# TactJam_Assembly.net
KiCad netlist of a schematic drawn in EasyEDA
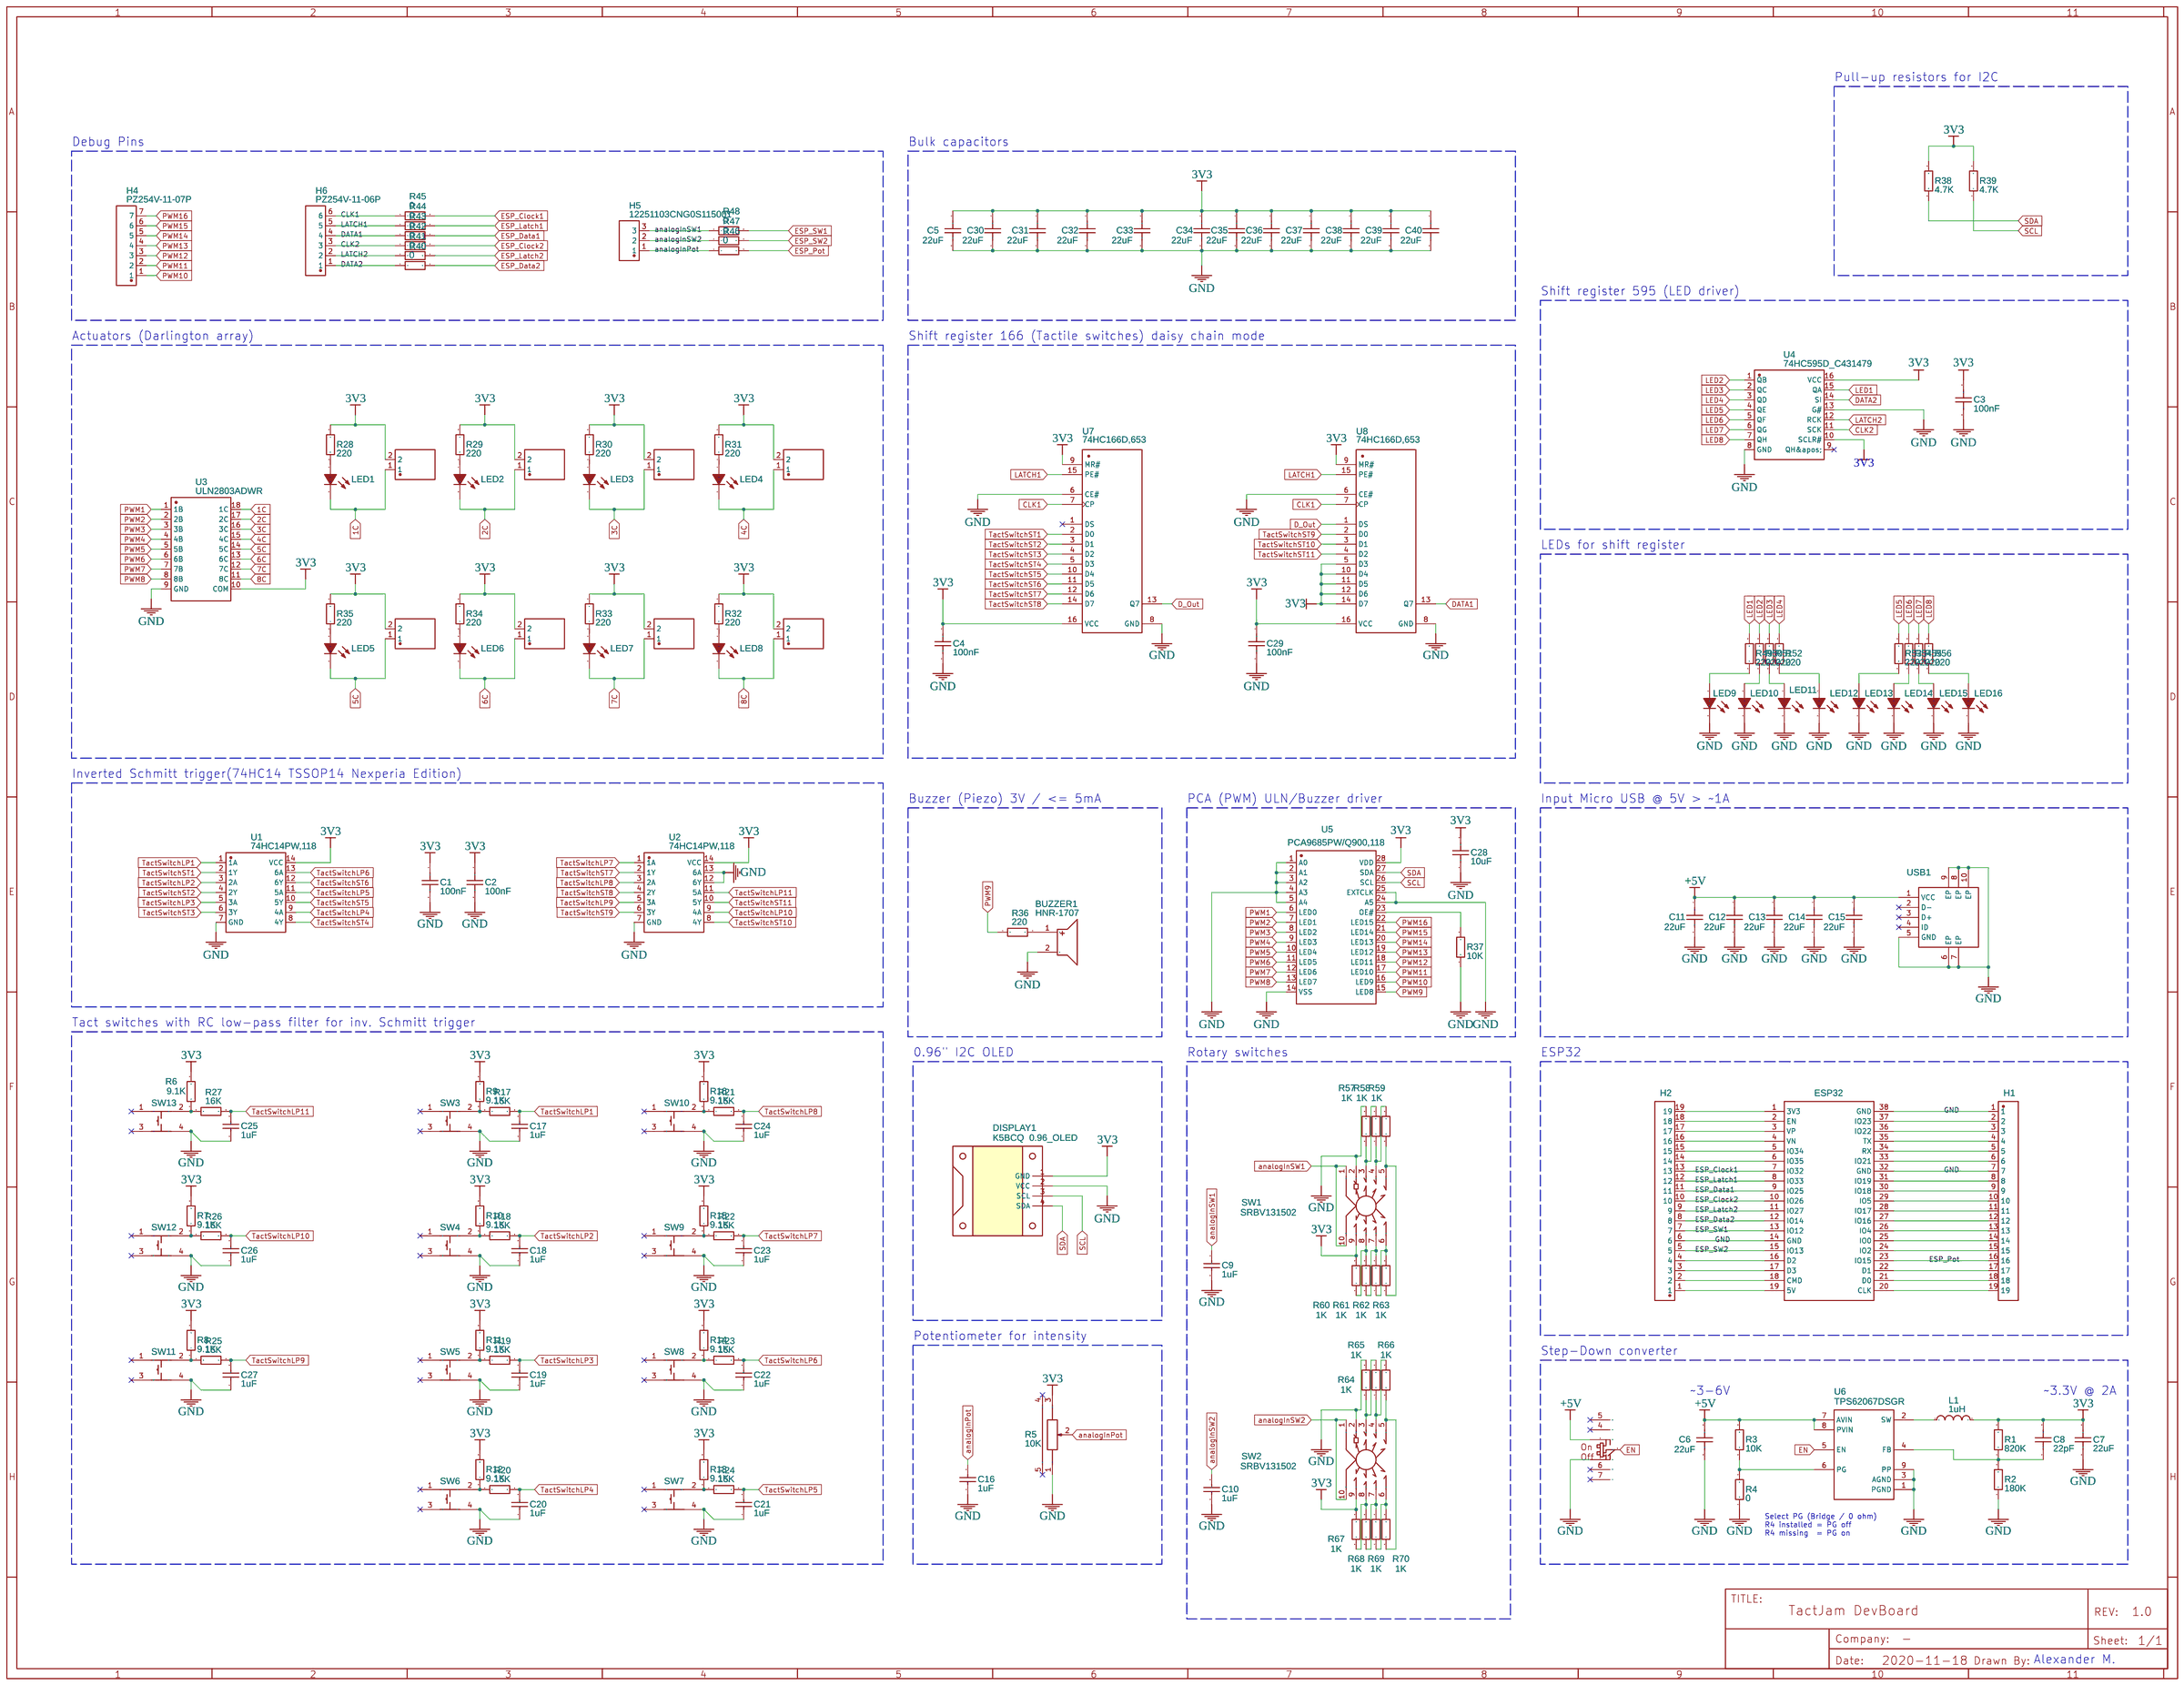
[diagram p0: schematic sheet]

(export (version "E")
  (design (tool "Eeschema 10.0.6"))
  (components
    (comp (ref "BUZZER1")
      (value "HNR-1707")
      (fields (field (name "BOM_Supplier Part") "C129400"))
      (libsource (lib "") (part "HNR-1707"))
    )
    (comp (ref "C1")
      (value "100nF")
      (fields
        (field (name "BOM_Manufacturer Part") "CL05B104KB54PNC")
        (field (name "BOM_Supplier Part") "C307331")
      )
      (libsource (lib "") (part "CL05B104KB54PNC"))
    )
    (comp (ref "C2")
      (value "100nF")
      (fields
        (field (name "BOM_Manufacturer Part") "CL05B104KB54PNC")
        (field (name "BOM_Supplier Part") "C307331")
      )
      (libsource (lib "") (part "CL05B104KB54PNC"))
    )
    (comp (ref "C3")
      (value "100nF")
      (fields
        (field (name "BOM_Manufacturer Part") "CL05B104KB54PNC")
        (field (name "BOM_Supplier Part") "C307331")
      )
      (libsource (lib "") (part "CL05B104KB54PNC"))
    )
    (comp (ref "C4")
      (value "100nF")
      (fields
        (field (name "BOM_Manufacturer Part") "CL05B104KB54PNC")
        (field (name "BOM_Supplier Part") "C307331")
      )
      (libsource (lib "") (part "CL05B104KB54PNC"))
    )
    (comp (ref "C5")
      (value "22uF")
      (fields
        (field (name "BOM_Manufacturer Part") "CL10A226MQ8NRNC")
        (field (name "BOM_Supplier Part") "C59461")
      )
      (libsource (lib "") (part "CL10A226MQ8NRNC"))
    )
    (comp (ref "C6")
      (value "22uF")
      (fields
        (field (name "BOM_Manufacturer Part") "CL10A226MQ8NRNC")
        (field (name "BOM_Supplier Part") "C59461")
      )
      (libsource (lib "") (part "CL10A226MQ8NRNC"))
    )
    (comp (ref "C7")
      (value "22uF")
      (fields
        (field (name "BOM_Manufacturer Part") "CL10A226MQ8NRNC")
        (field (name "BOM_Supplier Part") "C59461")
      )
      (libsource (lib "") (part "CL10A226MQ8NRNC_1"))
    )
    (comp (ref "C8")
      (value "22pF")
      (fields
        (field (name "BOM_Manufacturer Part") "CL05C220JB5NNNC")
        (field (name "BOM_Supplier Part") "C70464")
      )
      (libsource (lib "") (part "CL05C220JB5NNNC"))
    )
    (comp (ref "C9")
      (value "1uF")
      (fields
        (field (name "BOM_Manufacturer Part") "CL10B105KA8NNNC")
        (field (name "BOM_Supplier Part") "C29936")
      )
      (libsource (lib "") (part "CL10B105KA8NNNC"))
    )
    (comp (ref "C10")
      (value "1uF")
      (fields
        (field (name "BOM_Manufacturer Part") "CL10B105KA8NNNC")
        (field (name "BOM_Supplier Part") "C29936")
      )
      (libsource (lib "") (part "CL10B105KA8NNNC"))
    )
    (comp (ref "C11")
      (value "22uF")
      (fields
        (field (name "BOM_Manufacturer Part") "CL10A226MQ8NRNC")
        (field (name "BOM_Supplier Part") "C59461")
      )
      (libsource (lib "") (part "CL10A226MQ8NRNC"))
    )
    (comp (ref "C12")
      (value "22uF")
      (fields
        (field (name "BOM_Manufacturer Part") "CL10A226MQ8NRNC")
        (field (name "BOM_Supplier Part") "C59461")
      )
      (libsource (lib "") (part "CL10A226MQ8NRNC"))
    )
    (comp (ref "C13")
      (value "22uF")
      (fields
        (field (name "BOM_Manufacturer Part") "CL10A226MQ8NRNC")
        (field (name "BOM_Supplier Part") "C59461")
      )
      (libsource (lib "") (part "CL10A226MQ8NRNC"))
    )
    (comp (ref "C14")
      (value "22uF")
      (fields
        (field (name "BOM_Manufacturer Part") "CL10A226MQ8NRNC")
        (field (name "BOM_Supplier Part") "C59461")
      )
      (libsource (lib "") (part "CL10A226MQ8NRNC"))
    )
    (comp (ref "C15")
      (value "22uF")
      (fields
        (field (name "BOM_Manufacturer Part") "CL10A226MQ8NRNC")
        (field (name "BOM_Supplier Part") "C59461")
      )
      (libsource (lib "") (part "CL10A226MQ8NRNC"))
    )
    (comp (ref "C16")
      (value "1uF")
      (fields
        (field (name "BOM_Manufacturer Part") "CL10B105KA8NNNC")
        (field (name "BOM_Supplier Part") "C29936")
      )
      (libsource (lib "") (part "CL10B105KA8NNNC"))
    )
    (comp (ref "C17")
      (value "1uF")
      (fields
        (field (name "BOM_Manufacturer Part") "CL10B105KA8NNNC")
        (field (name "BOM_Supplier Part") "C29936")
      )
      (libsource (lib "") (part "CL10B105KA8NNNC"))
    )
    (comp (ref "C18")
      (value "1uF")
      (fields
        (field (name "BOM_Manufacturer Part") "CL10B105KA8NNNC")
        (field (name "BOM_Supplier Part") "C29936")
      )
      (libsource (lib "") (part "CL10B105KA8NNNC"))
    )
    (comp (ref "C19")
      (value "1uF")
      (fields
        (field (name "BOM_Manufacturer Part") "CL10B105KA8NNNC")
        (field (name "BOM_Supplier Part") "C29936")
      )
      (libsource (lib "") (part "CL10B105KA8NNNC"))
    )
    (comp (ref "C20")
      (value "1uF")
      (fields
        (field (name "BOM_Manufacturer Part") "CL10B105KA8NNNC")
        (field (name "BOM_Supplier Part") "C29936")
      )
      (libsource (lib "") (part "CL10B105KA8NNNC"))
    )
    (comp (ref "C21")
      (value "1uF")
      (fields
        (field (name "BOM_Manufacturer Part") "CL10B105KA8NNNC")
        (field (name "BOM_Supplier Part") "C29936")
      )
      (libsource (lib "") (part "CL10B105KA8NNNC"))
    )
    (comp (ref "C22")
      (value "1uF")
      (fields
        (field (name "BOM_Manufacturer Part") "CL10B105KA8NNNC")
        (field (name "BOM_Supplier Part") "C29936")
      )
      (libsource (lib "") (part "CL10B105KA8NNNC"))
    )
    (comp (ref "C23")
      (value "1uF")
      (fields
        (field (name "BOM_Manufacturer Part") "CL10B105KA8NNNC")
        (field (name "BOM_Supplier Part") "C29936")
      )
      (libsource (lib "") (part "CL10B105KA8NNNC"))
    )
    (comp (ref "C24")
      (value "1uF")
      (fields
        (field (name "BOM_Manufacturer Part") "CL10B105KA8NNNC")
        (field (name "BOM_Supplier Part") "C29936")
      )
      (libsource (lib "") (part "CL10B105KA8NNNC"))
    )
    (comp (ref "C25")
      (value "1uF")
      (fields
        (field (name "BOM_Manufacturer Part") "CL10B105KA8NNNC")
        (field (name "BOM_Supplier Part") "C29936")
      )
      (libsource (lib "") (part "CL10B105KA8NNNC"))
    )
    (comp (ref "C26")
      (value "1uF")
      (fields
        (field (name "BOM_Manufacturer Part") "CL10B105KA8NNNC")
        (field (name "BOM_Supplier Part") "C29936")
      )
      (libsource (lib "") (part "CL10B105KA8NNNC"))
    )
    (comp (ref "C27")
      (value "1uF")
      (fields
        (field (name "BOM_Manufacturer Part") "CL10B105KA8NNNC")
        (field (name "BOM_Supplier Part") "C29936")
      )
      (libsource (lib "") (part "CL10B105KA8NNNC"))
    )
    (comp (ref "C28")
      (value "10uF")
      (fields
        (field (name "BOM_Manufacturer Part") "CL10A106MA8NRNC")
        (field (name "BOM_Supplier Part") "C96446")
      )
      (libsource (lib "") (part "CL10A106MA8NRNC"))
    )
    (comp (ref "C29")
      (value "100nF")
      (fields
        (field (name "BOM_Manufacturer Part") "CL05B104KB54PNC")
        (field (name "BOM_Supplier Part") "C307331")
      )
      (libsource (lib "") (part "CL05B104KB54PNC"))
    )
    (comp (ref "C30")
      (value "22uF")
      (fields
        (field (name "BOM_Manufacturer Part") "CL10A226MQ8NRNC")
        (field (name "BOM_Supplier Part") "C59461")
      )
      (libsource (lib "") (part "CL10A226MQ8NRNC"))
    )
    (comp (ref "C31")
      (value "22uF")
      (fields
        (field (name "BOM_Manufacturer Part") "CL10A226MQ8NRNC")
        (field (name "BOM_Supplier Part") "C59461")
      )
      (libsource (lib "") (part "CL10A226MQ8NRNC"))
    )
    (comp (ref "C32")
      (value "22uF")
      (fields
        (field (name "BOM_Manufacturer Part") "CL10A226MQ8NRNC")
        (field (name "BOM_Supplier Part") "C59461")
      )
      (libsource (lib "") (part "CL10A226MQ8NRNC"))
    )
    (comp (ref "C33")
      (value "22uF")
      (fields
        (field (name "BOM_Manufacturer Part") "CL10A226MQ8NRNC")
        (field (name "BOM_Supplier Part") "C59461")
      )
      (libsource (lib "") (part "CL10A226MQ8NRNC"))
    )
    (comp (ref "C34")
      (value "22uF")
      (fields
        (field (name "BOM_Manufacturer Part") "CL10A226MQ8NRNC")
        (field (name "BOM_Supplier Part") "C59461")
      )
      (libsource (lib "") (part "CL10A226MQ8NRNC"))
    )
    (comp (ref "C35")
      (value "22uF")
      (fields
        (field (name "BOM_Manufacturer Part") "CL10A226MQ8NRNC")
        (field (name "BOM_Supplier Part") "C59461")
      )
      (libsource (lib "") (part "CL10A226MQ8NRNC"))
    )
    (comp (ref "C36")
      (value "22uF")
      (fields
        (field (name "BOM_Manufacturer Part") "CL10A226MQ8NRNC")
        (field (name "BOM_Supplier Part") "C59461")
      )
      (libsource (lib "") (part "CL10A226MQ8NRNC"))
    )
    (comp (ref "C37")
      (value "22uF")
      (fields
        (field (name "BOM_Manufacturer Part") "CL10A226MQ8NRNC")
        (field (name "BOM_Supplier Part") "C59461")
      )
      (libsource (lib "") (part "CL10A226MQ8NRNC"))
    )
    (comp (ref "C38")
      (value "22uF")
      (fields
        (field (name "BOM_Manufacturer Part") "CL10A226MQ8NRNC")
        (field (name "BOM_Supplier Part") "C59461")
      )
      (libsource (lib "") (part "CL10A226MQ8NRNC"))
    )
    (comp (ref "C39")
      (value "22uF")
      (fields
        (field (name "BOM_Manufacturer Part") "CL10A226MQ8NRNC")
        (field (name "BOM_Supplier Part") "C59461")
      )
      (libsource (lib "") (part "CL10A226MQ8NRNC"))
    )
    (comp (ref "C40")
      (value "22uF")
      (fields
        (field (name "BOM_Manufacturer Part") "CL10A226MQ8NRNC")
        (field (name "BOM_Supplier Part") "C59461")
      )
      (libsource (lib "") (part "CL10A226MQ8NRNC"))
    )
    (comp (ref "CONNECTOR1")
      (value "Connector")
      (fields (field (name "BOM_Supplier Part") "C132463"))
      (libsource (lib "") (part "2501SB-2P"))
    )
    (comp (ref "CONNECTOR2")
      (value "Connector")
      (fields (field (name "BOM_Supplier Part") "C63855"))
      (libsource (lib "") (part "2501SB-2P"))
    )
    (comp (ref "CONNECTOR3")
      (value "Connector")
      (fields (field (name "BOM_Supplier Part") "C132463"))
      (libsource (lib "") (part "2501SB-2P"))
    )
    (comp (ref "CONNECTOR4")
      (value "Connector")
      (fields (field (name "BOM_Supplier Part") "C132463"))
      (libsource (lib "") (part "2501SB-2P"))
    )
    (comp (ref "CONNECTOR5")
      (value "Connector")
      (fields (field (name "BOM_Supplier Part") "C132463"))
      (libsource (lib "") (part "2501SB-2P"))
    )
    (comp (ref "CONNECTOR6")
      (value "Connector")
      (fields (field (name "BOM_Supplier Part") "C132463"))
      (libsource (lib "") (part "2501SB-2P"))
    )
    (comp (ref "CONNECTOR7")
      (value "Connector")
      (fields (field (name "BOM_Supplier Part") "C132463"))
      (libsource (lib "") (part "2501SB-2P"))
    )
    (comp (ref "CONNECTOR8")
      (value "Connector")
      (fields (field (name "BOM_Supplier Part") "C132463"))
      (libsource (lib "") (part "2501SB-2P"))
    )
    (comp (ref "DISPLAY1")
      (value "K5BCQ  0.96_OLED")
      (fields (field (name "BOM_Manufacturer Part") "0.96 OLED"))
      (libsource (lib "") (part "K5BCQ  0.96_OLED"))
    )
    (comp (ref "ESP1") (value "ESP32") (libsource (lib "") (part "ESP32")))
    (comp (ref "H1") (value "C247840") (libsource (lib "") (part "C247840_1")))
    (comp (ref "H2") (value "C247840") (libsource (lib "") (part "C247840")))
    (comp (ref "H4")
      (value "PZ254V-11-07P")
      (fields (field (name "BOM_Supplier Part") "C492406"))
      (libsource (lib "") (part "PZ254V-11-07P"))
    )
    (comp (ref "H5")
      (value "12251103CNG0S115001")
      (fields (field (name "BOM_Supplier Part") "C429954"))
      (libsource (lib "") (part "12251103CNG0S115001"))
    )
    (comp (ref "H6")
      (value "PZ254V-11-06P")
      (fields (field (name "BOM_Supplier Part") "C492405"))
      (libsource (lib "") (part "PZ254V-11-06P"))
    )
    (comp (ref "L1")
      (value "1uH")
      (fields
        (field (name "BOM_Manufacturer Part") "LQH44PN1R0NP0L")
        (field (name "BOM_Supplier Part") "C98026")
      )
      (libsource (lib "") (part "LQH44PN1R0NP0L"))
    )
    (comp (ref "LED1")
      (value "19-217/GHC-YR1S2/3T")
      (fields (field (name "BOM_Supplier Part") "C72043"))
      (libsource (lib "") (part "19-217/GHC-YR1S2/3T"))
    )
    (comp (ref "LED2")
      (value "19-217/GHC-YR1S2/3T")
      (fields (field (name "BOM_Supplier Part") "C72043"))
      (libsource (lib "") (part "19-217/GHC-YR1S2/3T"))
    )
    (comp (ref "LED3")
      (value "19-217/GHC-YR1S2/3T")
      (fields (field (name "BOM_Supplier Part") "C72043"))
      (libsource (lib "") (part "19-217/GHC-YR1S2/3T"))
    )
    (comp (ref "LED4")
      (value "19-217/GHC-YR1S2/3T")
      (fields (field (name "BOM_Supplier Part") "C72043"))
      (libsource (lib "") (part "19-217/GHC-YR1S2/3T"))
    )
    (comp (ref "LED5")
      (value "19-217/GHC-YR1S2/3T")
      (fields (field (name "BOM_Supplier Part") "C72043"))
      (libsource (lib "") (part "19-217/GHC-YR1S2/3T"))
    )
    (comp (ref "LED6")
      (value "19-217/GHC-YR1S2/3T")
      (fields (field (name "BOM_Supplier Part") "C72043"))
      (libsource (lib "") (part "19-217/GHC-YR1S2/3T"))
    )
    (comp (ref "LED7")
      (value "19-217/GHC-YR1S2/3T")
      (fields (field (name "BOM_Supplier Part") "C72043"))
      (libsource (lib "") (part "19-217/GHC-YR1S2/3T"))
    )
    (comp (ref "LED8")
      (value "19-217/GHC-YR1S2/3T")
      (fields (field (name "BOM_Supplier Part") "C72043"))
      (libsource (lib "") (part "19-217/GHC-YR1S2/3T"))
    )
    (comp (ref "LED9")
      (value "19-217/GHC-YR1S2/3T")
      (fields (field (name "BOM_Supplier Part") "C72043"))
      (libsource (lib "") (part "19-217/GHC-YR1S2/3T"))
    )
    (comp (ref "LED10")
      (value "19-217/GHC-YR1S2/3T")
      (fields (field (name "BOM_Supplier Part") "C72043"))
      (libsource (lib "") (part "19-217/GHC-YR1S2/3T"))
    )
    (comp (ref "LED11")
      (value "19-217/GHC-YR1S2/3T")
      (fields (field (name "BOM_Supplier Part") "C72043"))
      (libsource (lib "") (part "19-217/GHC-YR1S2/3T"))
    )
    (comp (ref "LED12")
      (value "19-217/GHC-YR1S2/3T")
      (fields (field (name "BOM_Supplier Part") "C72043"))
      (libsource (lib "") (part "19-217/GHC-YR1S2/3T"))
    )
    (comp (ref "LED13")
      (value "19-217/GHC-YR1S2/3T")
      (fields (field (name "BOM_Supplier Part") "C72043"))
      (libsource (lib "") (part "19-217/GHC-YR1S2/3T"))
    )
    (comp (ref "LED14")
      (value "19-217/GHC-YR1S2/3T")
      (fields (field (name "BOM_Supplier Part") "C72043"))
      (libsource (lib "") (part "19-217/GHC-YR1S2/3T"))
    )
    (comp (ref "LED15")
      (value "19-217/GHC-YR1S2/3T")
      (fields (field (name "BOM_Supplier Part") "C72043"))
      (libsource (lib "") (part "19-217/GHC-YR1S2/3T"))
    )
    (comp (ref "LED16")
      (value "19-217/GHC-YR1S2/3T")
      (fields (field (name "BOM_Supplier Part") "C72043"))
      (libsource (lib "") (part "19-217/GHC-YR1S2/3T"))
    )
    (comp (ref "R1")
      (value "820K")
      (fields
        (field (name "BOM_Manufacturer Part") "TC0325B8203T5E")
        (field (name "BOM_Supplier Part") "C53198")
      )
      (libsource (lib "") (part "TC0325B8203T5E"))
    )
    (comp (ref "R2")
      (value "180K")
      (fields
        (field (name "BOM_Manufacturer Part") "0603WAF1803T5E")
        (field (name "BOM_Supplier Part") "C22827")
      )
      (libsource (lib "") (part "0603WAF1803T5E"))
    )
    (comp (ref "R3")
      (value "10K")
      (fields
        (field (name "BOM_Manufacturer Part") "0603WAF1002T5E")
        (field (name "BOM_Supplier Part") "C25804")
      )
      (libsource (lib "") (part "0603WAF1002T5E"))
    )
    (comp (ref "R4")
      (value "0")
      (fields
        (field (name "BOM_Manufacturer Part") "0603WAF0000T5E")
        (field (name "BOM_Supplier Part") "C21189")
      )
      (libsource (lib "") (part "0603WAF0000T5E_1"))
    )
    (comp (ref "R5")
      (value "10K")
      (fields
        (field (name "BOM_Manufacturer Part") "RK09K1130A5R")
        (field (name "BOM_Supplier Part") "C209779")
      )
      (libsource (lib "") (part "RK09K1130A5R"))
    )
    (comp (ref "R6")
      (value "9.1K")
      (fields
        (field (name "BOM_Manufacturer Part") "TC0350D9101T5E")
        (field (name "BOM_Supplier Part") "C98730")
      )
      (libsource (lib "") (part "TC0350D9101T5E"))
    )
    (comp (ref "R7")
      (value "9.1K")
      (fields
        (field (name "BOM_Manufacturer Part") "TC0350D9101T5E")
        (field (name "BOM_Supplier Part") "C98730")
      )
      (libsource (lib "") (part "TC0350D9101T5E"))
    )
    (comp (ref "R8")
      (value "9.1K")
      (fields
        (field (name "BOM_Manufacturer Part") "TC0350D9101T5E")
        (field (name "BOM_Supplier Part") "C98730")
      )
      (libsource (lib "") (part "TC0350D9101T5E"))
    )
    (comp (ref "R9")
      (value "9.1K")
      (fields
        (field (name "BOM_Manufacturer Part") "TC0350D9101T5E")
        (field (name "BOM_Supplier Part") "C98730")
      )
      (libsource (lib "") (part "TC0350D9101T5E"))
    )
    (comp (ref "R10")
      (value "9.1K")
      (fields
        (field (name "BOM_Manufacturer Part") "TC0350D9101T5E")
        (field (name "BOM_Supplier Part") "C98730")
      )
      (libsource (lib "") (part "TC0350D9101T5E"))
    )
    (comp (ref "R11")
      (value "9.1K")
      (fields
        (field (name "BOM_Manufacturer Part") "TC0350D9101T5E")
        (field (name "BOM_Supplier Part") "C98730")
      )
      (libsource (lib "") (part "TC0350D9101T5E"))
    )
    (comp (ref "R12")
      (value "9.1K")
      (fields
        (field (name "BOM_Manufacturer Part") "TC0350D9101T5E")
        (field (name "BOM_Supplier Part") "C98730")
      )
      (libsource (lib "") (part "TC0350D9101T5E"))
    )
    (comp (ref "R13")
      (value "9.1K")
      (fields
        (field (name "BOM_Manufacturer Part") "TC0350D9101T5E")
        (field (name "BOM_Supplier Part") "C98730")
      )
      (libsource (lib "") (part "TC0350D9101T5E"))
    )
    (comp (ref "R14")
      (value "9.1K")
      (fields
        (field (name "BOM_Manufacturer Part") "TC0350D9101T5E")
        (field (name "BOM_Supplier Part") "C98730")
      )
      (libsource (lib "") (part "TC0350D9101T5E"))
    )
    (comp (ref "R15")
      (value "9.1K")
      (fields
        (field (name "BOM_Manufacturer Part") "TC0350D9101T5E")
        (field (name "BOM_Supplier Part") "C98730")
      )
      (libsource (lib "") (part "TC0350D9101T5E"))
    )
    (comp (ref "R16")
      (value "9.1K")
      (fields
        (field (name "BOM_Manufacturer Part") "TC0350D9101T5E")
        (field (name "BOM_Supplier Part") "C98730")
      )
      (libsource (lib "") (part "TC0350D9101T5E"))
    )
    (comp (ref "R17")
      (value "16K")
      (fields
        (field (name "BOM_Manufacturer Part") "TC0325B1602T5E")
        (field (name "BOM_Supplier Part") "C139125")
      )
      (libsource (lib "") (part "TC0325B1602T5E"))
    )
    (comp (ref "R18")
      (value "16K")
      (fields
        (field (name "BOM_Manufacturer Part") "TC0325B1602T5E")
        (field (name "BOM_Supplier Part") "C139125")
      )
      (libsource (lib "") (part "TC0325B1602T5E"))
    )
    (comp (ref "R19")
      (value "16K")
      (fields
        (field (name "BOM_Manufacturer Part") "TC0325B1602T5E")
        (field (name "BOM_Supplier Part") "C139125")
      )
      (libsource (lib "") (part "TC0325B1602T5E"))
    )
    (comp (ref "R20")
      (value "16K")
      (fields
        (field (name "BOM_Manufacturer Part") "TC0325B1602T5E")
        (field (name "BOM_Supplier Part") "C139125")
      )
      (libsource (lib "") (part "TC0325B1602T5E"))
    )
    (comp (ref "R21")
      (value "16K")
      (fields
        (field (name "BOM_Manufacturer Part") "TC0325B1602T5E")
        (field (name "BOM_Supplier Part") "C139125")
      )
      (libsource (lib "") (part "TC0325B1602T5E"))
    )
    (comp (ref "R22")
      (value "16K")
      (fields
        (field (name "BOM_Manufacturer Part") "TC0325B1602T5E")
        (field (name "BOM_Supplier Part") "C139125")
      )
      (libsource (lib "") (part "TC0325B1602T5E"))
    )
    (comp (ref "R23")
      (value "16K")
      (fields
        (field (name "BOM_Manufacturer Part") "TC0325B1602T5E")
        (field (name "BOM_Supplier Part") "C139125")
      )
      (libsource (lib "") (part "TC0325B1602T5E"))
    )
    (comp (ref "R24")
      (value "16K")
      (fields
        (field (name "BOM_Manufacturer Part") "TC0325B1602T5E")
        (field (name "BOM_Supplier Part") "C139125")
      )
      (libsource (lib "") (part "TC0325B1602T5E"))
    )
    (comp (ref "R25")
      (value "16K")
      (fields
        (field (name "BOM_Manufacturer Part") "TC0325B1602T5E")
        (field (name "BOM_Supplier Part") "C139125")
      )
      (libsource (lib "") (part "TC0325B1602T5E"))
    )
    (comp (ref "R26")
      (value "16K")
      (fields
        (field (name "BOM_Manufacturer Part") "TC0325B1602T5E")
        (field (name "BOM_Supplier Part") "C139125")
      )
      (libsource (lib "") (part "TC0325B1602T5E"))
    )
    (comp (ref "R27")
      (value "16K")
      (fields
        (field (name "BOM_Manufacturer Part") "TC0325B1602T5E")
        (field (name "BOM_Supplier Part") "C139125")
      )
      (libsource (lib "") (part "TC0325B1602T5E"))
    )
    (comp (ref "R28")
      (value "220")
      (fields
        (field (name "BOM_Manufacturer Part") "0603WAF2200T5E")
        (field (name "BOM_Supplier Part") "C22962")
      )
      (libsource (lib "") (part "0603WAF2200T5E"))
    )
    (comp (ref "R29")
      (value "220")
      (fields
        (field (name "BOM_Manufacturer Part") "0603WAF2200T5E")
        (field (name "BOM_Supplier Part") "C22962")
      )
      (libsource (lib "") (part "0603WAF2200T5E"))
    )
    (comp (ref "R30")
      (value "220")
      (fields
        (field (name "BOM_Manufacturer Part") "0603WAF2200T5E")
        (field (name "BOM_Supplier Part") "C22962")
      )
      (libsource (lib "") (part "0603WAF2200T5E"))
    )
    (comp (ref "R31")
      (value "220")
      (fields
        (field (name "BOM_Manufacturer Part") "0603WAF2200T5E")
        (field (name "BOM_Supplier Part") "C22962")
      )
      (libsource (lib "") (part "0603WAF2200T5E"))
    )
    (comp (ref "R32")
      (value "220")
      (fields
        (field (name "BOM_Manufacturer Part") "0603WAF2200T5E")
        (field (name "BOM_Supplier Part") "C22962")
      )
      (libsource (lib "") (part "0603WAF2200T5E"))
    )
    (comp (ref "R33")
      (value "220")
      (fields
        (field (name "BOM_Manufacturer Part") "0603WAF2200T5E")
        (field (name "BOM_Supplier Part") "C22962")
      )
      (libsource (lib "") (part "0603WAF2200T5E"))
    )
    (comp (ref "R34")
      (value "220")
      (fields
        (field (name "BOM_Manufacturer Part") "0603WAF2200T5E")
        (field (name "BOM_Supplier Part") "C22962")
      )
      (libsource (lib "") (part "0603WAF2200T5E"))
    )
    (comp (ref "R35")
      (value "220")
      (fields
        (field (name "BOM_Manufacturer Part") "0603WAF2200T5E")
        (field (name "BOM_Supplier Part") "C22962")
      )
      (libsource (lib "") (part "0603WAF2200T5E"))
    )
    (comp (ref "R36")
      (value "220")
      (fields
        (field (name "BOM_Manufacturer Part") "0603WAF2200T5E")
        (field (name "BOM_Supplier Part") "C22962")
      )
      (libsource (lib "") (part "0603WAF2200T5E_1"))
    )
    (comp (ref "R37")
      (value "10K")
      (fields
        (field (name "BOM_Manufacturer Part") "0603WAF1002T5E")
        (field (name "BOM_Supplier Part") "C25804")
      )
      (libsource (lib "") (part "0603WAF1002T5E"))
    )
    (comp (ref "R38")
      (value "4.7K")
      (fields
        (field (name "BOM_Manufacturer Part") "0603WAF4701T5E")
        (field (name "BOM_Supplier Part") "C23162")
      )
      (libsource (lib "") (part "0603WAF4701T5E"))
    )
    (comp (ref "R39")
      (value "4.7K")
      (fields
        (field (name "BOM_Manufacturer Part") "0603WAF4701T5E")
        (field (name "BOM_Supplier Part") "C23162")
      )
      (libsource (lib "") (part "0603WAF4701T5E"))
    )
    (comp (ref "R40")
      (value "0")
      (fields
        (field (name "BOM_Manufacturer Part") "0603WAF0000T5E")
        (field (name "BOM_Supplier Part") "C21189")
      )
      (libsource (lib "") (part "0603WAF0000T5E"))
    )
    (comp (ref "R41")
      (value "0")
      (fields
        (field (name "BOM_Manufacturer Part") "0603WAF0000T5E")
        (field (name "BOM_Supplier Part") "C21189")
      )
      (libsource (lib "") (part "0603WAF0000T5E"))
    )
    (comp (ref "R42")
      (value "0")
      (fields
        (field (name "BOM_Manufacturer Part") "0603WAF0000T5E")
        (field (name "BOM_Supplier Part") "C21189")
      )
      (libsource (lib "") (part "0603WAF0000T5E"))
    )
    (comp (ref "R43")
      (value "0")
      (fields
        (field (name "BOM_Manufacturer Part") "0603WAF0000T5E")
        (field (name "BOM_Supplier Part") "C21189")
      )
      (libsource (lib "") (part "0603WAF0000T5E"))
    )
    (comp (ref "R44")
      (value "0")
      (fields
        (field (name "BOM_Manufacturer Part") "0603WAF0000T5E")
        (field (name "BOM_Supplier Part") "C21189")
      )
      (libsource (lib "") (part "0603WAF0000T5E"))
    )
    (comp (ref "R45")
      (value "0")
      (fields
        (field (name "BOM_Manufacturer Part") "0603WAF0000T5E")
        (field (name "BOM_Supplier Part") "C21189")
      )
      (libsource (lib "") (part "0603WAF0000T5E"))
    )
    (comp (ref "R46")
      (value "0")
      (fields
        (field (name "BOM_Manufacturer Part") "0603WAF0000T5E")
        (field (name "BOM_Supplier Part") "C21189")
      )
      (libsource (lib "") (part "0603WAF0000T5E"))
    )
    (comp (ref "R47")
      (value "0")
      (fields
        (field (name "BOM_Manufacturer Part") "0603WAF0000T5E")
        (field (name "BOM_Supplier Part") "C21189")
      )
      (libsource (lib "") (part "0603WAF0000T5E"))
    )
    (comp (ref "R48")
      (value "0")
      (fields
        (field (name "BOM_Manufacturer Part") "0603WAF0000T5E")
        (field (name "BOM_Supplier Part") "C21189")
      )
      (libsource (lib "") (part "0603WAF0000T5E"))
    )
    (comp (ref "R49")
      (value "220")
      (fields
        (field (name "BOM_Manufacturer Part") "0603WAF2200T5E")
        (field (name "BOM_Supplier Part") "C22962")
      )
      (libsource (lib "") (part "0603WAF2200T5E"))
    )
    (comp (ref "R50")
      (value "220")
      (fields
        (field (name "BOM_Manufacturer Part") "0603WAF2200T5E")
        (field (name "BOM_Supplier Part") "C22962")
      )
      (libsource (lib "") (part "0603WAF2200T5E"))
    )
    (comp (ref "R51")
      (value "220")
      (fields
        (field (name "BOM_Manufacturer Part") "0603WAF2200T5E")
        (field (name "BOM_Supplier Part") "C22962")
      )
      (libsource (lib "") (part "0603WAF2200T5E"))
    )
    (comp (ref "R52")
      (value "220")
      (fields
        (field (name "BOM_Manufacturer Part") "0603WAF2200T5E")
        (field (name "BOM_Supplier Part") "C22962")
      )
      (libsource (lib "") (part "0603WAF2200T5E"))
    )
    (comp (ref "R53")
      (value "220")
      (fields
        (field (name "BOM_Manufacturer Part") "0603WAF2200T5E")
        (field (name "BOM_Supplier Part") "C22962")
      )
      (libsource (lib "") (part "0603WAF2200T5E"))
    )
    (comp (ref "R54")
      (value "220")
      (fields
        (field (name "BOM_Manufacturer Part") "0603WAF2200T5E")
        (field (name "BOM_Supplier Part") "C22962")
      )
      (libsource (lib "") (part "0603WAF2200T5E"))
    )
    (comp (ref "R55")
      (value "220")
      (fields
        (field (name "BOM_Manufacturer Part") "0603WAF2200T5E")
        (field (name "BOM_Supplier Part") "C22962")
      )
      (libsource (lib "") (part "0603WAF2200T5E"))
    )
    (comp (ref "R56")
      (value "220")
      (fields
        (field (name "BOM_Manufacturer Part") "0603WAF2200T5E")
        (field (name "BOM_Supplier Part") "C22962")
      )
      (libsource (lib "") (part "0603WAF2200T5E"))
    )
    (comp (ref "R57")
      (value "1K")
      (fields
        (field (name "BOM_Manufacturer Part") "0603WAF1001T5E")
        (field (name "BOM_Supplier Part") "C21190")
      )
      (libsource (lib "") (part "0603WAF1001T5E"))
    )
    (comp (ref "R58")
      (value "1K")
      (fields
        (field (name "BOM_Manufacturer Part") "0603WAF1001T5E")
        (field (name "BOM_Supplier Part") "C21190")
      )
      (libsource (lib "") (part "0603WAF1001T5E"))
    )
    (comp (ref "R59")
      (value "1K")
      (fields
        (field (name "BOM_Manufacturer Part") "0603WAF1001T5E")
        (field (name "BOM_Supplier Part") "C21190")
      )
      (libsource (lib "") (part "0603WAF1001T5E"))
    )
    (comp (ref "R60")
      (value "1K")
      (fields
        (field (name "BOM_Manufacturer Part") "0603WAF1001T5E")
        (field (name "BOM_Supplier Part") "C21190")
      )
      (libsource (lib "") (part "0603WAF1001T5E"))
    )
    (comp (ref "R61")
      (value "1K")
      (fields
        (field (name "BOM_Manufacturer Part") "0603WAF1001T5E")
        (field (name "BOM_Supplier Part") "C21190")
      )
      (libsource (lib "") (part "0603WAF1001T5E"))
    )
    (comp (ref "R62")
      (value "1K")
      (fields
        (field (name "BOM_Manufacturer Part") "0603WAF1001T5E")
        (field (name "BOM_Supplier Part") "C21190")
      )
      (libsource (lib "") (part "0603WAF1001T5E"))
    )
    (comp (ref "R63")
      (value "1K")
      (fields
        (field (name "BOM_Manufacturer Part") "0603WAF1001T5E")
        (field (name "BOM_Supplier Part") "C21190")
      )
      (libsource (lib "") (part "0603WAF1001T5E"))
    )
    (comp (ref "R64")
      (value "1K")
      (fields
        (field (name "BOM_Manufacturer Part") "0603WAF1001T5E")
        (field (name "BOM_Supplier Part") "C21190")
      )
      (libsource (lib "") (part "0603WAF1001T5E"))
    )
    (comp (ref "R65")
      (value "1K")
      (fields
        (field (name "BOM_Manufacturer Part") "0603WAF1001T5E")
        (field (name "BOM_Supplier Part") "C21190")
      )
      (libsource (lib "") (part "0603WAF1001T5E"))
    )
    (comp (ref "R66")
      (value "1K")
      (fields
        (field (name "BOM_Manufacturer Part") "0603WAF1001T5E")
        (field (name "BOM_Supplier Part") "C21190")
      )
      (libsource (lib "") (part "0603WAF1001T5E"))
    )
    (comp (ref "R67")
      (value "1K")
      (fields
        (field (name "BOM_Manufacturer Part") "0603WAF1001T5E")
        (field (name "BOM_Supplier Part") "C21190")
      )
      (libsource (lib "") (part "0603WAF1001T5E"))
    )
    (comp (ref "R68")
      (value "1K")
      (fields
        (field (name "BOM_Manufacturer Part") "0603WAF1001T5E")
        (field (name "BOM_Supplier Part") "C21190")
      )
      (libsource (lib "") (part "0603WAF1001T5E"))
    )
    (comp (ref "R69")
      (value "1K")
      (fields
        (field (name "BOM_Manufacturer Part") "0603WAF1001T5E")
        (field (name "BOM_Supplier Part") "C21190")
      )
      (libsource (lib "") (part "0603WAF1001T5E"))
    )
    (comp (ref "R70")
      (value "1K")
      (fields
        (field (name "BOM_Manufacturer Part") "0603WAF1001T5E")
        (field (name "BOM_Supplier Part") "C21190")
      )
      (libsource (lib "") (part "0603WAF1001T5E"))
    )
    (comp (ref "SW1")
      (value "SRBV131502")
      (fields (field (name "BOM_Supplier Part") "C255511"))
      (libsource (lib "") (part "SRBV131502"))
    )
    (comp (ref "SW2")
      (value "SRBV131502")
      (fields (field (name "BOM_Supplier Part") "C255511"))
      (libsource (lib "") (part "SRBV131502"))
    )
    (comp (ref "SW3")
      (value "TS-1003T-26")
      (fields (field (name "BOM_Supplier Part") "C455235"))
      (libsource (lib "") (part "TS-1003T-26"))
    )
    (comp (ref "SW4")
      (value "TS-1003T-26")
      (fields (field (name "BOM_Supplier Part") "C455235"))
      (libsource (lib "") (part "TS-1003T-26"))
    )
    (comp (ref "SW5")
      (value "TS-1003T-26")
      (fields (field (name "BOM_Supplier Part") "C455235"))
      (libsource (lib "") (part "TS-1003T-26"))
    )
    (comp (ref "SW6")
      (value "TS-1003T-26")
      (fields (field (name "BOM_Supplier Part") "C455235"))
      (libsource (lib "") (part "TS-1003T-26"))
    )
    (comp (ref "SW7")
      (value "TS-1003T-26")
      (fields (field (name "BOM_Supplier Part") "C455235"))
      (libsource (lib "") (part "TS-1003T-26"))
    )
    (comp (ref "SW8")
      (value "TS-1003T-26")
      (fields (field (name "BOM_Supplier Part") "C455235"))
      (libsource (lib "") (part "TS-1003T-26"))
    )
    (comp (ref "SW9")
      (value "TS-1003T-26")
      (fields (field (name "BOM_Supplier Part") "C455235"))
      (libsource (lib "") (part "TS-1003T-26"))
    )
    (comp (ref "SW10")
      (value "TS-1003T-26")
      (fields (field (name "BOM_Supplier Part") "C455235"))
      (libsource (lib "") (part "TS-1003T-26"))
    )
    (comp (ref "SW11")
      (value "TS-1003T-26")
      (fields (field (name "BOM_Supplier Part") "C455235"))
      (libsource (lib "") (part "TS-1003T-26"))
    )
    (comp (ref "SW12")
      (value "TS-1003T-26")
      (fields (field (name "BOM_Supplier Part") "C455235"))
      (libsource (lib "") (part "TS-1003T-26"))
    )
    (comp (ref "SW13")
      (value "TS-1003T-26")
      (fields (field (name "BOM_Supplier Part") "C455235"))
      (libsource (lib "") (part "TS-1003T-26"))
    )
    (comp (ref "SWSTEP1")
      (value "K3-1296S-E1")
      (fields (field (name "BOM_Supplier Part") "C128955"))
      (libsource (lib "") (part "K3-1296S-E1"))
    )
    (comp (ref "U1")
      (value "74HC14PW,118")
      (fields (field (name "BOM_Supplier Part") "C5606"))
      (libsource (lib "") (part "74HC14PW,118"))
    )
    (comp (ref "U2")
      (value "74HC14PW,118")
      (fields (field (name "BOM_Supplier Part") "C5606"))
      (libsource (lib "") (part "74HC14PW,118"))
    )
    (comp (ref "U3")
      (value "ULN2803ADWR")
      (fields (field (name "BOM_Supplier Part") "C9683"))
      (libsource (lib "") (part "ULN2803ADWR"))
    )
    (comp (ref "U4")
      (value "74HC595D_C431479")
      (fields (field (name "BOM_Manufacturer Part") "74HC595D") (field (name "BOM_Supplier Part") "C431479"))
      (libsource (lib "") (part "74HC595D_C431479"))
    )
    (comp (ref "U5")
      (value "PCA9685PW/Q900,118")
      (fields (field (name "BOM_Supplier Part") "C92206"))
      (libsource (lib "") (part "PCA9685PW/Q900,118"))
    )
    (comp (ref "U6")
      (value "TPS62067DSGR")
      (fields (field (name "BOM_Supplier Part") "C7098"))
      (libsource (lib "") (part "TPS62067DSGR"))
    )
    (comp (ref "U7")
      (value "74HC166D,653")
      (fields (field (name "BOM_Supplier Part") "C131891"))
      (libsource (lib "") (part "74HC166D,653"))
    )
    (comp (ref "U8")
      (value "74HC166D,653")
      (fields (field (name "BOM_Supplier Part") "C131891"))
      (libsource (lib "") (part "74HC166D,653"))
    )
    (comp (ref "USB1")
      (value "105017-0001")
      (fields (field (name "BOM_Supplier Part") "C136000"))
      (libsource (lib "") (part "105017-0001"))
    )
  )
  (nets
    (net (code "1") (name "+5V") (class "Default")
      (node (ref "C11") (pin "1") (pinfunction "1_1") (pintype "unspecified"))
      (node (ref "C12") (pin "1") (pinfunction "1_1") (pintype "unspecified"))
      (node (ref "C13") (pin "1") (pinfunction "1_1") (pintype "unspecified"))
      (node (ref "C14") (pin "1") (pinfunction "1_1") (pintype "unspecified"))
      (node (ref "C15") (pin "1") (pinfunction "1_1") (pintype "unspecified"))
      (node (ref "C6") (pin "1") (pinfunction "1_1") (pintype "unspecified"))
      (node (ref "R3") (pin "2") (pinfunction "2_2") (pintype "input"))
      (node (ref "SWSTEP1") (pin "3") (pinfunction "3_3") (pintype "unspecified"))
      (node (ref "U6") (pin "7") (pinfunction "AVIN_7") (pintype "passive"))
      (node (ref "U6") (pin "8") (pinfunction "PVIN_8") (pintype "passive"))
      (node (ref "USB1") (pin "1") (pinfunction "VCC_1") (pintype "unspecified"))
    )
    (net (code "2") (name "1C") (class "Default")
      (node (ref "CONNECTOR1") (pin "1") (pinfunction "1_1") (pintype "unspecified"))
      (node (ref "LED1") (pin "2") (pinfunction "C_2") (pintype "input"))
      (node (ref "U3") (pin "18") (pinfunction "1C_18") (pintype "unspecified"))
    )
    (net (code "3") (name "2C") (class "Default")
      (node (ref "CONNECTOR2") (pin "1") (pinfunction "1_1") (pintype "unspecified"))
      (node (ref "LED2") (pin "2") (pinfunction "C_2") (pintype "input"))
      (node (ref "U3") (pin "17") (pinfunction "2C_17") (pintype "unspecified"))
    )
    (net (code "4") (name "3C") (class "Default")
      (node (ref "CONNECTOR3") (pin "1") (pinfunction "1_1") (pintype "unspecified"))
      (node (ref "LED3") (pin "2") (pinfunction "C_2") (pintype "input"))
      (node (ref "U3") (pin "16") (pinfunction "3C_16") (pintype "unspecified"))
    )
    (net (code "5") (name "3V3") (class "Default")
      (node (ref "C1") (pin "1") (pinfunction "1_1") (pintype "unspecified"))
      (node (ref "C2") (pin "1") (pinfunction "1_1") (pintype "unspecified"))
      (node (ref "C28") (pin "2") (pinfunction "2_2") (pintype "unspecified"))
      (node (ref "C29") (pin "1") (pinfunction "1_1") (pintype "unspecified"))
      (node (ref "C3") (pin "1") (pinfunction "1_1") (pintype "unspecified"))
      (node (ref "C30") (pin "1") (pinfunction "1_1") (pintype "unspecified"))
      (node (ref "C31") (pin "1") (pinfunction "1_1") (pintype "unspecified"))
      (node (ref "C32") (pin "1") (pinfunction "1_1") (pintype "unspecified"))
      (node (ref "C33") (pin "1") (pinfunction "1_1") (pintype "unspecified"))
      (node (ref "C34") (pin "1") (pinfunction "1_1") (pintype "unspecified"))
      (node (ref "C35") (pin "1") (pinfunction "1_1") (pintype "unspecified"))
      (node (ref "C36") (pin "1") (pinfunction "1_1") (pintype "unspecified"))
      (node (ref "C37") (pin "1") (pinfunction "1_1") (pintype "unspecified"))
      (node (ref "C38") (pin "1") (pinfunction "1_1") (pintype "unspecified"))
      (node (ref "C39") (pin "1") (pinfunction "1_1") (pintype "unspecified"))
      (node (ref "C4") (pin "1") (pinfunction "1_1") (pintype "unspecified"))
      (node (ref "C40") (pin "1") (pinfunction "1_1") (pintype "unspecified"))
      (node (ref "C5") (pin "1") (pinfunction "1_1") (pintype "unspecified"))
      (node (ref "C7") (pin "2") (pinfunction "2_2") (pintype "unspecified"))
      (node (ref "C8") (pin "2") (pinfunction "2_2") (pintype "unspecified"))
      (node (ref "CONNECTOR1") (pin "2") (pinfunction "2_2") (pintype "unspecified"))
      (node (ref "CONNECTOR2") (pin "2") (pinfunction "2_2") (pintype "unspecified"))
      (node (ref "CONNECTOR3") (pin "2") (pinfunction "2_2") (pintype "unspecified"))
      (node (ref "CONNECTOR4") (pin "2") (pinfunction "2_2") (pintype "unspecified"))
      (node (ref "CONNECTOR5") (pin "2") (pinfunction "2_2") (pintype "unspecified"))
      (node (ref "CONNECTOR6") (pin "2") (pinfunction "2_2") (pintype "unspecified"))
      (node (ref "CONNECTOR7") (pin "2") (pinfunction "2_2") (pintype "unspecified"))
      (node (ref "CONNECTOR8") (pin "2") (pinfunction "2_2") (pintype "unspecified"))
      (node (ref "DISPLAY1") (pin "1") (pinfunction "GND_1") (pintype "unspecified"))
      (node (ref "L1") (pin "2") (pinfunction "2_2") (pintype "unspecified"))
      (node (ref "R1") (pin "2") (pinfunction "2_2") (pintype "input"))
      (node (ref "R10") (pin "2") (pinfunction "2_2") (pintype "input"))
      (node (ref "R11") (pin "2") (pinfunction "2_2") (pintype "input"))
      (node (ref "R12") (pin "2") (pinfunction "2_2") (pintype "input"))
      (node (ref "R13") (pin "2") (pinfunction "2_2") (pintype "input"))
      (node (ref "R14") (pin "2") (pinfunction "2_2") (pintype "input"))
      (node (ref "R15") (pin "2") (pinfunction "2_2") (pintype "input"))
      (node (ref "R16") (pin "2") (pinfunction "2_2") (pintype "input"))
      (node (ref "R28") (pin "2") (pinfunction "2_2") (pintype "input"))
      (node (ref "R29") (pin "2") (pinfunction "2_2") (pintype "input"))
      (node (ref "R30") (pin "2") (pinfunction "2_2") (pintype "input"))
      (node (ref "R31") (pin "2") (pinfunction "2_2") (pintype "input"))
      (node (ref "R32") (pin "2") (pinfunction "2_2") (pintype "input"))
      (node (ref "R33") (pin "2") (pinfunction "2_2") (pintype "input"))
      (node (ref "R34") (pin "2") (pinfunction "2_2") (pintype "input"))
      (node (ref "R35") (pin "2") (pinfunction "2_2") (pintype "input"))
      (node (ref "R38") (pin "2") (pinfunction "2_2") (pintype "input"))
      (node (ref "R39") (pin "2") (pinfunction "2_2") (pintype "input"))
      (node (ref "R5") (pin "3") (pinfunction "3_3") (pintype "unspecified"))
      (node (ref "R6") (pin "2") (pinfunction "2_2") (pintype "input"))
      (node (ref "R60") (pin "2") (pinfunction "2_2") (pintype "input"))
      (node (ref "R67") (pin "2") (pinfunction "2_2") (pintype "input"))
      (node (ref "R7") (pin "2") (pinfunction "2_2") (pintype "input"))
      (node (ref "R8") (pin "2") (pinfunction "2_2") (pintype "input"))
      (node (ref "R9") (pin "2") (pinfunction "2_2") (pintype "input"))
      (node (ref "SW1") (pin "9") (pinfunction "9_9") (pintype "unspecified"))
      (node (ref "SW2") (pin "9") (pinfunction "9_9") (pintype "unspecified"))
      (node (ref "U1") (pin "14") (pinfunction "VCC_14") (pintype "unspecified"))
      (node (ref "U2") (pin "14") (pinfunction "VCC_14") (pintype "unspecified"))
      (node (ref "U3") (pin "10") (pinfunction "COM_10") (pintype "unspecified"))
      (node (ref "U4") (pin "10") (pinfunction "SCLR#_10") (pintype "unspecified"))
      (node (ref "U4") (pin "16") (pinfunction "VCC_16") (pintype "unspecified"))
      (node (ref "U5") (pin "28") (pinfunction "VDD_28") (pintype "unspecified"))
      (node (ref "U7") (pin "16") (pinfunction "VCC_16") (pintype "passive"))
      (node (ref "U7") (pin "9") (pinfunction "MR#_9") (pintype "unspecified"))
      (node (ref "U8") (pin "10") (pinfunction "D4_10") (pintype "unspecified"))
      (node (ref "U8") (pin "11") (pinfunction "D5_11") (pintype "unspecified"))
      (node (ref "U8") (pin "12") (pinfunction "D6_12") (pintype "unspecified"))
      (node (ref "U8") (pin "14") (pinfunction "D7_14") (pintype "unspecified"))
      (node (ref "U8") (pin "16") (pinfunction "VCC_16") (pintype "passive"))
      (node (ref "U8") (pin "5") (pinfunction "D3_5") (pintype "unspecified"))
      (node (ref "U8") (pin "9") (pinfunction "MR#_9") (pintype "unspecified"))
    )
    (net (code "6") (name "4C") (class "Default")
      (node (ref "CONNECTOR4") (pin "1") (pinfunction "1_1") (pintype "unspecified"))
      (node (ref "LED4") (pin "2") (pinfunction "C_2") (pintype "input"))
      (node (ref "U3") (pin "15") (pinfunction "4C_15") (pintype "unspecified"))
    )
    (net (code "7") (name "5C") (class "Default")
      (node (ref "CONNECTOR5") (pin "1") (pinfunction "1_1") (pintype "unspecified"))
      (node (ref "LED5") (pin "2") (pinfunction "C_2") (pintype "input"))
      (node (ref "U3") (pin "14") (pinfunction "5C_14") (pintype "unspecified"))
    )
    (net (code "8") (name "6C") (class "Default")
      (node (ref "CONNECTOR6") (pin "1") (pinfunction "1_1") (pintype "unspecified"))
      (node (ref "LED6") (pin "2") (pinfunction "C_2") (pintype "input"))
      (node (ref "U3") (pin "13") (pinfunction "6C_13") (pintype "unspecified"))
    )
    (net (code "9") (name "7C") (class "Default")
      (node (ref "CONNECTOR7") (pin "1") (pinfunction "1_1") (pintype "unspecified"))
      (node (ref "LED7") (pin "2") (pinfunction "C_2") (pintype "input"))
      (node (ref "U3") (pin "12") (pinfunction "7C_12") (pintype "unspecified"))
    )
    (net (code "10") (name "8C") (class "Default")
      (node (ref "CONNECTOR8") (pin "1") (pinfunction "1_1") (pintype "unspecified"))
      (node (ref "LED8") (pin "2") (pinfunction "C_2") (pintype "input"))
      (node (ref "U3") (pin "11") (pinfunction "8C_11") (pintype "unspecified"))
    )
    (net (code "11") (name "CLK1") (class "Default")
      (node (ref "H6") (pin "6") (pinfunction "6_6") (pintype "unspecified"))
      (node (ref "R45") (pin "1") (pinfunction "1_1") (pintype "input"))
      (node (ref "U7") (pin "7") (pinfunction "CP_7") (pintype "unspecified"))
      (node (ref "U8") (pin "7") (pinfunction "CP_7") (pintype "unspecified"))
    )
    (net (code "12") (name "CLK2") (class "Default")
      (node (ref "H6") (pin "3") (pinfunction "3_3") (pintype "unspecified"))
      (node (ref "R42") (pin "1") (pinfunction "1_1") (pintype "input"))
      (node (ref "U4") (pin "11") (pinfunction "SCK_11") (pintype "unspecified"))
    )
    (net (code "13") (name "DATA1") (class "Default")
      (node (ref "H6") (pin "4") (pinfunction "4_4") (pintype "unspecified"))
      (node (ref "R43") (pin "1") (pinfunction "1_1") (pintype "input"))
      (node (ref "U8") (pin "13") (pinfunction "Q7_13") (pintype "output"))
    )
    (net (code "14") (name "DATA2") (class "Default")
      (node (ref "H6") (pin "1") (pinfunction "1_1") (pintype "unspecified"))
      (node (ref "R40") (pin "1") (pinfunction "1_1") (pintype "input"))
      (node (ref "U4") (pin "14") (pinfunction "SI_14") (pintype "unspecified"))
    )
    (net (code "15") (name "D_Out") (class "Default")
      (node (ref "U7") (pin "13") (pinfunction "Q7_13") (pintype "output"))
      (node (ref "U8") (pin "1") (pinfunction "DS_1") (pintype "unspecified"))
    )
    (net (code "16") (name "EN") (class "Default")
      (node (ref "SWSTEP1") (pin "2") (pinfunction "2_2") (pintype "unspecified"))
      (node (ref "U6") (pin "5") (pinfunction "EN_5") (pintype "unspecified"))
    )
    (net (code "17") (name "ESP_Clock1") (class "Default")
      (node (ref "ESP1") (pin "7") (pinfunction "IO32_7") (pintype "unspecified"))
      (node (ref "H2") (pin "13") (pinfunction "13_13") (pintype "unspecified"))
      (node (ref "R45") (pin "2") (pinfunction "2_2") (pintype "input"))
    )
    (net (code "18") (name "ESP_Clock2") (class "Default")
      (node (ref "ESP1") (pin "10") (pinfunction "IO26_10") (pintype "unspecified"))
      (node (ref "H2") (pin "10") (pinfunction "10_10") (pintype "unspecified"))
      (node (ref "R42") (pin "2") (pinfunction "2_2") (pintype "input"))
    )
    (net (code "19") (name "ESP_Data1") (class "Default")
      (node (ref "ESP1") (pin "9") (pinfunction "IO25_9") (pintype "unspecified"))
      (node (ref "H2") (pin "11") (pinfunction "11_11") (pintype "unspecified"))
      (node (ref "R43") (pin "2") (pinfunction "2_2") (pintype "input"))
    )
    (net (code "20") (name "ESP_Data2") (class "Default")
      (node (ref "ESP1") (pin "12") (pinfunction "IO14_12") (pintype "unspecified"))
      (node (ref "H2") (pin "8") (pinfunction "8_8") (pintype "unspecified"))
      (node (ref "R40") (pin "2") (pinfunction "2_2") (pintype "input"))
    )
    (net (code "21") (name "ESP_Latch1") (class "Default")
      (node (ref "ESP1") (pin "8") (pinfunction "IO33_8") (pintype "unspecified"))
      (node (ref "H2") (pin "12") (pinfunction "12_12") (pintype "unspecified"))
      (node (ref "R44") (pin "2") (pinfunction "2_2") (pintype "input"))
    )
    (net (code "22") (name "ESP_Latch2") (class "Default")
      (node (ref "ESP1") (pin "11") (pinfunction "IO27_11") (pintype "unspecified"))
      (node (ref "H2") (pin "9") (pinfunction "9_9") (pintype "unspecified"))
      (node (ref "R41") (pin "2") (pinfunction "2_2") (pintype "input"))
    )
    (net (code "23") (name "ESP_Pot") (class "Default")
      (node (ref "ESP1") (pin "23") (pinfunction "IO15_23") (pintype "unspecified"))
      (node (ref "H1") (pin "16") (pinfunction "16_16") (pintype "unspecified"))
      (node (ref "R46") (pin "2") (pinfunction "2_2") (pintype "input"))
    )
    (net (code "24") (name "ESP_SW1") (class "Default")
      (node (ref "ESP1") (pin "13") (pinfunction "IO12_13") (pintype "unspecified"))
      (node (ref "H2") (pin "7") (pinfunction "7_7") (pintype "unspecified"))
      (node (ref "R48") (pin "2") (pinfunction "2_2") (pintype "input"))
    )
    (net (code "25") (name "ESP_SW2") (class "Default")
      (node (ref "ESP1") (pin "15") (pinfunction "IO13_15") (pintype "unspecified"))
      (node (ref "H2") (pin "5") (pinfunction "5_5") (pintype "unspecified"))
      (node (ref "R47") (pin "2") (pinfunction "2_2") (pintype "input"))
    )
    (net (code "26") (name "GND") (class "Default")
      (node (ref "BUZZER1") (pin "2") (pinfunction "2_2") (pintype "unspecified"))
      (node (ref "C1") (pin "2") (pinfunction "2_2") (pintype "unspecified"))
      (node (ref "C10") (pin "1") (pinfunction "1_1") (pintype "input"))
      (node (ref "C11") (pin "2") (pinfunction "2_2") (pintype "unspecified"))
      (node (ref "C12") (pin "2") (pinfunction "2_2") (pintype "unspecified"))
      (node (ref "C13") (pin "2") (pinfunction "2_2") (pintype "unspecified"))
      (node (ref "C14") (pin "2") (pinfunction "2_2") (pintype "unspecified"))
      (node (ref "C15") (pin "2") (pinfunction "2_2") (pintype "unspecified"))
      (node (ref "C16") (pin "1") (pinfunction "1_1") (pintype "input"))
      (node (ref "C17") (pin "1") (pinfunction "1_1") (pintype "input"))
      (node (ref "C18") (pin "1") (pinfunction "1_1") (pintype "input"))
      (node (ref "C19") (pin "1") (pinfunction "1_1") (pintype "input"))
      (node (ref "C2") (pin "2") (pinfunction "2_2") (pintype "unspecified"))
      (node (ref "C20") (pin "1") (pinfunction "1_1") (pintype "input"))
      (node (ref "C21") (pin "1") (pinfunction "1_1") (pintype "input"))
      (node (ref "C22") (pin "1") (pinfunction "1_1") (pintype "input"))
      (node (ref "C23") (pin "1") (pinfunction "1_1") (pintype "input"))
      (node (ref "C24") (pin "1") (pinfunction "1_1") (pintype "input"))
      (node (ref "C25") (pin "1") (pinfunction "1_1") (pintype "input"))
      (node (ref "C26") (pin "1") (pinfunction "1_1") (pintype "input"))
      (node (ref "C27") (pin "1") (pinfunction "1_1") (pintype "input"))
      (node (ref "C28") (pin "1") (pinfunction "1_1") (pintype "unspecified"))
      (node (ref "C29") (pin "2") (pinfunction "2_2") (pintype "unspecified"))
      (node (ref "C3") (pin "2") (pinfunction "2_2") (pintype "unspecified"))
      (node (ref "C30") (pin "2") (pinfunction "2_2") (pintype "unspecified"))
      (node (ref "C31") (pin "2") (pinfunction "2_2") (pintype "unspecified"))
      (node (ref "C32") (pin "2") (pinfunction "2_2") (pintype "unspecified"))
      (node (ref "C33") (pin "2") (pinfunction "2_2") (pintype "unspecified"))
      (node (ref "C34") (pin "2") (pinfunction "2_2") (pintype "unspecified"))
      (node (ref "C35") (pin "2") (pinfunction "2_2") (pintype "unspecified"))
      (node (ref "C36") (pin "2") (pinfunction "2_2") (pintype "unspecified"))
      (node (ref "C37") (pin "2") (pinfunction "2_2") (pintype "unspecified"))
      (node (ref "C38") (pin "2") (pinfunction "2_2") (pintype "unspecified"))
      (node (ref "C39") (pin "2") (pinfunction "2_2") (pintype "unspecified"))
      (node (ref "C4") (pin "2") (pinfunction "2_2") (pintype "unspecified"))
      (node (ref "C40") (pin "2") (pinfunction "2_2") (pintype "unspecified"))
      (node (ref "C5") (pin "2") (pinfunction "2_2") (pintype "unspecified"))
      (node (ref "C6") (pin "2") (pinfunction "2_2") (pintype "unspecified"))
      (node (ref "C7") (pin "1") (pinfunction "1_1") (pintype "unspecified"))
      (node (ref "C9") (pin "1") (pinfunction "1_1") (pintype "input"))
      (node (ref "DISPLAY1") (pin "2") (pinfunction "VCC_2") (pintype "unspecified"))
      (node (ref "ESP1") (pin "14") (pinfunction "GND_14") (pintype "unspecified"))
      (node (ref "ESP1") (pin "32") (pinfunction "GND_32") (pintype "unspecified"))
      (node (ref "ESP1") (pin "38") (pinfunction "GND_38") (pintype "unspecified"))
      (node (ref "H1") (pin "1") (pinfunction "1_1") (pintype "unspecified"))
      (node (ref "H1") (pin "7") (pinfunction "7_7") (pintype "unspecified"))
      (node (ref "H2") (pin "6") (pinfunction "6_6") (pintype "unspecified"))
      (node (ref "LED10") (pin "2") (pinfunction "C_2") (pintype "input"))
      (node (ref "LED11") (pin "2") (pinfunction "C_2") (pintype "input"))
      (node (ref "LED12") (pin "2") (pinfunction "C_2") (pintype "input"))
      (node (ref "LED13") (pin "2") (pinfunction "C_2") (pintype "input"))
      (node (ref "LED14") (pin "2") (pinfunction "C_2") (pintype "input"))
      (node (ref "LED15") (pin "2") (pinfunction "C_2") (pintype "input"))
      (node (ref "LED16") (pin "2") (pinfunction "C_2") (pintype "input"))
      (node (ref "LED9") (pin "2") (pinfunction "C_2") (pintype "input"))
      (node (ref "R2") (pin "1") (pinfunction "1_1") (pintype "input"))
      (node (ref "R37") (pin "1") (pinfunction "1_1") (pintype "input"))
      (node (ref "R4") (pin "1") (pinfunction "1_1") (pintype "input"))
      (node (ref "R5") (pin "1") (pinfunction "1_1") (pintype "unspecified"))
      (node (ref "R57") (pin "2") (pinfunction "2_2") (pintype "input"))
      (node (ref "R64") (pin "2") (pinfunction "2_2") (pintype "input"))
      (node (ref "SW1") (pin "2") (pinfunction "2_2") (pintype "unspecified"))
      (node (ref "SW10") (pin "4") (pinfunction "4_4") (pintype "unspecified"))
      (node (ref "SW11") (pin "4") (pinfunction "4_4") (pintype "unspecified"))
      (node (ref "SW12") (pin "4") (pinfunction "4_4") (pintype "unspecified"))
      (node (ref "SW13") (pin "4") (pinfunction "4_4") (pintype "unspecified"))
      (node (ref "SW2") (pin "2") (pinfunction "2_2") (pintype "unspecified"))
      (node (ref "SW3") (pin "4") (pinfunction "4_4") (pintype "unspecified"))
      (node (ref "SW4") (pin "4") (pinfunction "4_4") (pintype "unspecified"))
      (node (ref "SW5") (pin "4") (pinfunction "4_4") (pintype "unspecified"))
      (node (ref "SW6") (pin "4") (pinfunction "4_4") (pintype "unspecified"))
      (node (ref "SW7") (pin "4") (pinfunction "4_4") (pintype "unspecified"))
      (node (ref "SW8") (pin "4") (pinfunction "4_4") (pintype "unspecified"))
      (node (ref "SW9") (pin "4") (pinfunction "4_4") (pintype "unspecified"))
      (node (ref "SWSTEP1") (pin "1") (pinfunction "1_1") (pintype "unspecified"))
      (node (ref "U1") (pin "7") (pinfunction "GND_7") (pintype "unspecified"))
      (node (ref "U2") (pin "12") (pinfunction "6Y_12") (pintype "unspecified"))
      (node (ref "U2") (pin "13") (pinfunction "6A_13") (pintype "unspecified"))
      (node (ref "U2") (pin "7") (pinfunction "GND_7") (pintype "unspecified"))
      (node (ref "U3") (pin "9") (pinfunction "GND_9") (pintype "unspecified"))
      (node (ref "U4") (pin "13") (pinfunction "G#_13") (pintype "unspecified"))
      (node (ref "U4") (pin "8") (pinfunction "GND_8") (pintype "unspecified"))
      (node (ref "U5") (pin "1") (pinfunction "A0_1") (pintype "unspecified"))
      (node (ref "U5") (pin "14") (pinfunction "VSS_14") (pintype "unspecified"))
      (node (ref "U5") (pin "2") (pinfunction "A1_2") (pintype "unspecified"))
      (node (ref "U5") (pin "24") (pinfunction "A5_24") (pintype "unspecified"))
      (node (ref "U5") (pin "25") (pinfunction "EXTCLK_25") (pintype "unspecified"))
      (node (ref "U5") (pin "3") (pinfunction "A2_3") (pintype "unspecified"))
      (node (ref "U5") (pin "4") (pinfunction "A3_4") (pintype "unspecified"))
      (node (ref "U5") (pin "5") (pinfunction "A4_5") (pintype "unspecified"))
      (node (ref "U6") (pin "1") (pinfunction "PGND_1") (pintype "passive"))
      (node (ref "U6") (pin "3") (pinfunction "AGND_3") (pintype "passive"))
      (node (ref "U6") (pin "9") (pinfunction "PP_9") (pintype "passive"))
      (node (ref "U7") (pin "6") (pinfunction "CE#_6") (pintype "unspecified"))
      (node (ref "U7") (pin "8") (pinfunction "GND_8") (pintype "passive"))
      (node (ref "U8") (pin "6") (pinfunction "CE#_6") (pintype "unspecified"))
      (node (ref "U8") (pin "8") (pinfunction "GND_8") (pintype "passive"))
      (node (ref "USB1") (pin "10") (pinfunction "EP_10") (pintype "unspecified"))
      (node (ref "USB1") (pin "5") (pinfunction "GND_5") (pintype "unspecified"))
      (node (ref "USB1") (pin "6") (pinfunction "EP_6") (pintype "unspecified"))
      (node (ref "USB1") (pin "7") (pinfunction "EP_7") (pintype "unspecified"))
      (node (ref "USB1") (pin "8") (pinfunction "EP_8") (pintype "unspecified"))
      (node (ref "USB1") (pin "9") (pinfunction "EP_9") (pintype "unspecified"))
    )
    (net (code "27") (name "LATCH1") (class "Default")
      (node (ref "H6") (pin "5") (pinfunction "5_5") (pintype "unspecified"))
      (node (ref "R44") (pin "1") (pinfunction "1_1") (pintype "input"))
      (node (ref "U7") (pin "15") (pinfunction "PE#_15") (pintype "unspecified"))
      (node (ref "U8") (pin "15") (pinfunction "PE#_15") (pintype "unspecified"))
    )
    (net (code "28") (name "LATCH2") (class "Default")
      (node (ref "H6") (pin "2") (pinfunction "2_2") (pintype "unspecified"))
      (node (ref "R41") (pin "1") (pinfunction "1_1") (pintype "input"))
      (node (ref "U4") (pin "12") (pinfunction "RCK_12") (pintype "unspecified"))
    )
    (net (code "29") (name "LED1") (class "Default")
      (node (ref "R49") (pin "2") (pinfunction "2_2") (pintype "input"))
      (node (ref "U4") (pin "15") (pinfunction "QA_15") (pintype "unspecified"))
    )
    (net (code "30") (name "LED2") (class "Default")
      (node (ref "R50") (pin "2") (pinfunction "2_2") (pintype "input"))
      (node (ref "U4") (pin "1") (pinfunction "QB_1") (pintype "unspecified"))
    )
    (net (code "31") (name "LED3") (class "Default")
      (node (ref "R51") (pin "2") (pinfunction "2_2") (pintype "input"))
      (node (ref "U4") (pin "2") (pinfunction "QC_2") (pintype "unspecified"))
    )
    (net (code "32") (name "LED4") (class "Default")
      (node (ref "R52") (pin "2") (pinfunction "2_2") (pintype "input"))
      (node (ref "U4") (pin "3") (pinfunction "QD_3") (pintype "unspecified"))
    )
    (net (code "33") (name "LED5") (class "Default")
      (node (ref "R53") (pin "2") (pinfunction "2_2") (pintype "input"))
      (node (ref "U4") (pin "4") (pinfunction "QE_4") (pintype "unspecified"))
    )
    (net (code "34") (name "LED6") (class "Default")
      (node (ref "R54") (pin "2") (pinfunction "2_2") (pintype "input"))
      (node (ref "U4") (pin "5") (pinfunction "QF_5") (pintype "unspecified"))
    )
    (net (code "35") (name "LED7") (class "Default")
      (node (ref "R55") (pin "2") (pinfunction "2_2") (pintype "input"))
      (node (ref "U4") (pin "6") (pinfunction "QG_6") (pintype "unspecified"))
    )
    (net (code "36") (name "LED8") (class "Default")
      (node (ref "R56") (pin "2") (pinfunction "2_2") (pintype "input"))
      (node (ref "U4") (pin "7") (pinfunction "QH_7") (pintype "unspecified"))
    )
    (net (code "37") (name "Net-(BUZZER1-Pad1)") (class "Default")
      (node (ref "BUZZER1") (pin "1") (pinfunction "1_1") (pintype "unspecified"))
      (node (ref "R36") (pin "2") (pinfunction "2_2") (pintype "input"))
    )
    (net (code "38") (name "Net-(ESP1-3V3)") (class "Default")
      (node (ref "ESP1") (pin "1") (pinfunction "3V3_1") (pintype "unspecified"))
      (node (ref "H2") (pin "19") (pinfunction "19_19") (pintype "unspecified"))
    )
    (net (code "39") (name "Net-(ESP1-5V)") (class "Default")
      (node (ref "ESP1") (pin "19") (pinfunction "5V_19") (pintype "unspecified"))
      (node (ref "H2") (pin "1") (pinfunction "1_1") (pintype "unspecified"))
    )
    (net (code "40") (name "Net-(ESP1-CLK)") (class "Default")
      (node (ref "ESP1") (pin "20") (pinfunction "CLK_20") (pintype "unspecified"))
      (node (ref "H1") (pin "19") (pinfunction "19_19") (pintype "unspecified"))
    )
    (net (code "41") (name "Net-(ESP1-CMD)") (class "Default")
      (node (ref "ESP1") (pin "18") (pinfunction "CMD_18") (pintype "unspecified"))
      (node (ref "H2") (pin "2") (pinfunction "2_2") (pintype "unspecified"))
    )
    (net (code "42") (name "Net-(ESP1-D0)") (class "Default")
      (node (ref "ESP1") (pin "21") (pinfunction "D0_21") (pintype "unspecified"))
      (node (ref "H1") (pin "18") (pinfunction "18_18") (pintype "unspecified"))
    )
    (net (code "43") (name "Net-(ESP1-D1)") (class "Default")
      (node (ref "ESP1") (pin "22") (pinfunction "D1_22") (pintype "unspecified"))
      (node (ref "H1") (pin "17") (pinfunction "17_17") (pintype "unspecified"))
    )
    (net (code "44") (name "Net-(ESP1-D2)") (class "Default")
      (node (ref "ESP1") (pin "16") (pinfunction "D2_16") (pintype "unspecified"))
      (node (ref "H2") (pin "4") (pinfunction "4_4") (pintype "unspecified"))
    )
    (net (code "45") (name "Net-(ESP1-D3)") (class "Default")
      (node (ref "ESP1") (pin "17") (pinfunction "D3_17") (pintype "unspecified"))
      (node (ref "H2") (pin "3") (pinfunction "3_3") (pintype "unspecified"))
    )
    (net (code "46") (name "Net-(ESP1-EN)") (class "Default")
      (node (ref "ESP1") (pin "2") (pinfunction "EN_2") (pintype "unspecified"))
      (node (ref "H2") (pin "18") (pinfunction "18_18") (pintype "unspecified"))
    )
    (net (code "47") (name "Net-(ESP1-IO0)") (class "Default")
      (node (ref "ESP1") (pin "25") (pinfunction "IO0_25") (pintype "unspecified"))
      (node (ref "H1") (pin "14") (pinfunction "14_14") (pintype "unspecified"))
    )
    (net (code "48") (name "Net-(ESP1-IO2)") (class "Default")
      (node (ref "ESP1") (pin "24") (pinfunction "IO2_24") (pintype "unspecified"))
      (node (ref "H1") (pin "15") (pinfunction "15_15") (pintype "unspecified"))
    )
    (net (code "49") (name "Net-(ESP1-IO4)") (class "Default")
      (node (ref "ESP1") (pin "26") (pinfunction "IO4_26") (pintype "unspecified"))
      (node (ref "H1") (pin "13") (pinfunction "13_13") (pintype "unspecified"))
    )
    (net (code "50") (name "Net-(ESP1-IO5)") (class "Default")
      (node (ref "ESP1") (pin "29") (pinfunction "IO5_29") (pintype "unspecified"))
      (node (ref "H1") (pin "10") (pinfunction "10_10") (pintype "unspecified"))
    )
    (net (code "51") (name "Net-(ESP1-IO16)") (class "Default")
      (node (ref "ESP1") (pin "27") (pinfunction "IO16_27") (pintype "unspecified"))
      (node (ref "H1") (pin "12") (pinfunction "12_12") (pintype "unspecified"))
    )
    (net (code "52") (name "Net-(ESP1-IO17)") (class "Default")
      (node (ref "ESP1") (pin "28") (pinfunction "IO17_28") (pintype "unspecified"))
      (node (ref "H1") (pin "11") (pinfunction "11_11") (pintype "unspecified"))
    )
    (net (code "53") (name "Net-(ESP1-IO18)") (class "Default")
      (node (ref "ESP1") (pin "30") (pinfunction "IO18_30") (pintype "unspecified"))
      (node (ref "H1") (pin "9") (pinfunction "9_9") (pintype "unspecified"))
    )
    (net (code "54") (name "Net-(ESP1-IO19)") (class "Default")
      (node (ref "ESP1") (pin "31") (pinfunction "IO19_31") (pintype "unspecified"))
      (node (ref "H1") (pin "8") (pinfunction "8_8") (pintype "unspecified"))
    )
    (net (code "55") (name "Net-(ESP1-IO21)") (class "Default")
      (node (ref "ESP1") (pin "33") (pinfunction "IO21_33") (pintype "unspecified"))
      (node (ref "H1") (pin "6") (pinfunction "6_6") (pintype "unspecified"))
    )
    (net (code "56") (name "Net-(ESP1-IO22)") (class "Default")
      (node (ref "ESP1") (pin "36") (pinfunction "IO22_36") (pintype "unspecified"))
      (node (ref "H1") (pin "3") (pinfunction "3_3") (pintype "unspecified"))
    )
    (net (code "57") (name "Net-(ESP1-IO23)") (class "Default")
      (node (ref "ESP1") (pin "37") (pinfunction "IO23_37") (pintype "unspecified"))
      (node (ref "H1") (pin "2") (pinfunction "2_2") (pintype "unspecified"))
    )
    (net (code "58") (name "Net-(ESP1-IO34)") (class "Default")
      (node (ref "ESP1") (pin "5") (pinfunction "IO34_5") (pintype "unspecified"))
      (node (ref "H2") (pin "15") (pinfunction "15_15") (pintype "unspecified"))
    )
    (net (code "59") (name "Net-(ESP1-IO35)") (class "Default")
      (node (ref "ESP1") (pin "6") (pinfunction "IO35_6") (pintype "unspecified"))
      (node (ref "H2") (pin "14") (pinfunction "14_14") (pintype "unspecified"))
    )
    (net (code "60") (name "Net-(ESP1-RX)") (class "Default")
      (node (ref "ESP1") (pin "34") (pinfunction "RX_34") (pintype "unspecified"))
      (node (ref "H1") (pin "5") (pinfunction "5_5") (pintype "unspecified"))
    )
    (net (code "61") (name "Net-(ESP1-TX)") (class "Default")
      (node (ref "ESP1") (pin "35") (pinfunction "TX_35") (pintype "unspecified"))
      (node (ref "H1") (pin "4") (pinfunction "4_4") (pintype "unspecified"))
    )
    (net (code "62") (name "Net-(ESP1-VN)") (class "Default")
      (node (ref "ESP1") (pin "4") (pinfunction "VN_4") (pintype "unspecified"))
      (node (ref "H2") (pin "16") (pinfunction "16_16") (pintype "unspecified"))
    )
    (net (code "63") (name "Net-(ESP1-VP)") (class "Default")
      (node (ref "ESP1") (pin "3") (pinfunction "VP_3") (pintype "unspecified"))
      (node (ref "H2") (pin "17") (pinfunction "17_17") (pintype "unspecified"))
    )
    (net (code "64") (name "Net-(LED1-A)") (class "Default")
      (node (ref "LED1") (pin "1") (pinfunction "A_1") (pintype "input"))
      (node (ref "R28") (pin "1") (pinfunction "1_1") (pintype "input"))
    )
    (net (code "65") (name "Net-(LED2-A)") (class "Default")
      (node (ref "LED2") (pin "1") (pinfunction "A_1") (pintype "input"))
      (node (ref "R29") (pin "1") (pinfunction "1_1") (pintype "input"))
    )
    (net (code "66") (name "Net-(LED3-A)") (class "Default")
      (node (ref "LED3") (pin "1") (pinfunction "A_1") (pintype "input"))
      (node (ref "R30") (pin "1") (pinfunction "1_1") (pintype "input"))
    )
    (net (code "67") (name "Net-(LED4-A)") (class "Default")
      (node (ref "LED4") (pin "1") (pinfunction "A_1") (pintype "input"))
      (node (ref "R31") (pin "1") (pinfunction "1_1") (pintype "input"))
    )
    (net (code "68") (name "Net-(LED5-A)") (class "Default")
      (node (ref "LED5") (pin "1") (pinfunction "A_1") (pintype "input"))
      (node (ref "R35") (pin "1") (pinfunction "1_1") (pintype "input"))
    )
    (net (code "69") (name "Net-(LED6-A)") (class "Default")
      (node (ref "LED6") (pin "1") (pinfunction "A_1") (pintype "input"))
      (node (ref "R34") (pin "1") (pinfunction "1_1") (pintype "input"))
    )
    (net (code "70") (name "Net-(LED7-A)") (class "Default")
      (node (ref "LED7") (pin "1") (pinfunction "A_1") (pintype "input"))
      (node (ref "R33") (pin "1") (pinfunction "1_1") (pintype "input"))
    )
    (net (code "71") (name "Net-(LED8-A)") (class "Default")
      (node (ref "LED8") (pin "1") (pinfunction "A_1") (pintype "input"))
      (node (ref "R32") (pin "1") (pinfunction "1_1") (pintype "input"))
    )
    (net (code "72") (name "Net-(LED9-A)") (class "Default")
      (node (ref "LED9") (pin "1") (pinfunction "A_1") (pintype "input"))
      (node (ref "R49") (pin "1") (pinfunction "1_1") (pintype "input"))
    )
    (net (code "73") (name "Net-(LED10-A)") (class "Default")
      (node (ref "LED10") (pin "1") (pinfunction "A_1") (pintype "input"))
      (node (ref "R50") (pin "1") (pinfunction "1_1") (pintype "input"))
    )
    (net (code "74") (name "Net-(LED11-A)") (class "Default")
      (node (ref "LED11") (pin "1") (pinfunction "A_1") (pintype "input"))
      (node (ref "R51") (pin "1") (pinfunction "1_1") (pintype "input"))
    )
    (net (code "75") (name "Net-(LED12-A)") (class "Default")
      (node (ref "LED12") (pin "1") (pinfunction "A_1") (pintype "input"))
      (node (ref "R52") (pin "1") (pinfunction "1_1") (pintype "input"))
    )
    (net (code "76") (name "Net-(LED13-A)") (class "Default")
      (node (ref "LED13") (pin "1") (pinfunction "A_1") (pintype "input"))
      (node (ref "R53") (pin "1") (pinfunction "1_1") (pintype "input"))
    )
    (net (code "77") (name "Net-(LED14-A)") (class "Default")
      (node (ref "LED14") (pin "1") (pinfunction "A_1") (pintype "input"))
      (node (ref "R54") (pin "1") (pinfunction "1_1") (pintype "input"))
    )
    (net (code "78") (name "Net-(LED15-A)") (class "Default")
      (node (ref "LED15") (pin "1") (pinfunction "A_1") (pintype "input"))
      (node (ref "R55") (pin "1") (pinfunction "1_1") (pintype "input"))
    )
    (net (code "79") (name "Net-(LED16-A)") (class "Default")
      (node (ref "LED16") (pin "1") (pinfunction "A_1") (pintype "input"))
      (node (ref "R56") (pin "1") (pinfunction "1_1") (pintype "input"))
    )
    (net (code "80") (name "Net-(R10-Pad1)") (class "Default")
      (node (ref "R10") (pin "1") (pinfunction "1_1") (pintype "input"))
      (node (ref "R18") (pin "1") (pinfunction "1_1") (pintype "unspecified"))
      (node (ref "SW4") (pin "2") (pinfunction "2_2") (pintype "unspecified"))
    )
    (net (code "81") (name "Net-(R11-Pad1)") (class "Default")
      (node (ref "R11") (pin "1") (pinfunction "1_1") (pintype "input"))
      (node (ref "R19") (pin "1") (pinfunction "1_1") (pintype "unspecified"))
      (node (ref "SW5") (pin "2") (pinfunction "2_2") (pintype "unspecified"))
    )
    (net (code "82") (name "Net-(R12-Pad1)") (class "Default")
      (node (ref "R12") (pin "1") (pinfunction "1_1") (pintype "input"))
      (node (ref "R20") (pin "1") (pinfunction "1_1") (pintype "unspecified"))
      (node (ref "SW6") (pin "2") (pinfunction "2_2") (pintype "unspecified"))
    )
    (net (code "83") (name "Net-(R13-Pad1)") (class "Default")
      (node (ref "R13") (pin "1") (pinfunction "1_1") (pintype "input"))
      (node (ref "R24") (pin "1") (pinfunction "1_1") (pintype "unspecified"))
      (node (ref "SW7") (pin "2") (pinfunction "2_2") (pintype "unspecified"))
    )
    (net (code "84") (name "Net-(R14-Pad1)") (class "Default")
      (node (ref "R14") (pin "1") (pinfunction "1_1") (pintype "input"))
      (node (ref "R23") (pin "1") (pinfunction "1_1") (pintype "unspecified"))
      (node (ref "SW8") (pin "2") (pinfunction "2_2") (pintype "unspecified"))
    )
    (net (code "85") (name "Net-(R15-Pad1)") (class "Default")
      (node (ref "R15") (pin "1") (pinfunction "1_1") (pintype "input"))
      (node (ref "R22") (pin "1") (pinfunction "1_1") (pintype "unspecified"))
      (node (ref "SW9") (pin "2") (pinfunction "2_2") (pintype "unspecified"))
    )
    (net (code "86") (name "Net-(R16-Pad1)") (class "Default")
      (node (ref "R16") (pin "1") (pinfunction "1_1") (pintype "input"))
      (node (ref "R21") (pin "1") (pinfunction "1_1") (pintype "unspecified"))
      (node (ref "SW10") (pin "2") (pinfunction "2_2") (pintype "unspecified"))
    )
    (net (code "87") (name "Net-(R17-Pad1)") (class "Default")
      (node (ref "R17") (pin "1") (pinfunction "1_1") (pintype "unspecified"))
      (node (ref "R9") (pin "1") (pinfunction "1_1") (pintype "input"))
      (node (ref "SW3") (pin "2") (pinfunction "2_2") (pintype "unspecified"))
    )
    (net (code "88") (name "Net-(R25-Pad1)") (class "Default")
      (node (ref "R25") (pin "1") (pinfunction "1_1") (pintype "unspecified"))
      (node (ref "R8") (pin "1") (pinfunction "1_1") (pintype "input"))
      (node (ref "SW11") (pin "2") (pinfunction "2_2") (pintype "unspecified"))
    )
    (net (code "89") (name "Net-(R26-Pad1)") (class "Default")
      (node (ref "R26") (pin "1") (pinfunction "1_1") (pintype "unspecified"))
      (node (ref "R7") (pin "1") (pinfunction "1_1") (pintype "input"))
      (node (ref "SW12") (pin "2") (pinfunction "2_2") (pintype "unspecified"))
    )
    (net (code "90") (name "Net-(R27-Pad1)") (class "Default")
      (node (ref "R27") (pin "1") (pinfunction "1_1") (pintype "unspecified"))
      (node (ref "R6") (pin "1") (pinfunction "1_1") (pintype "input"))
      (node (ref "SW13") (pin "2") (pinfunction "2_2") (pintype "unspecified"))
    )
    (net (code "91") (name "Net-(R57-Pad1)") (class "Default")
      (node (ref "R57") (pin "1") (pinfunction "1_1") (pintype "input"))
      (node (ref "R58") (pin "2") (pinfunction "2_2") (pintype "input"))
      (node (ref "SW1") (pin "3") (pinfunction "3_3") (pintype "unspecified"))
    )
    (net (code "92") (name "Net-(R58-Pad1)") (class "Default")
      (node (ref "R58") (pin "1") (pinfunction "1_1") (pintype "input"))
      (node (ref "R59") (pin "2") (pinfunction "2_2") (pintype "input"))
      (node (ref "SW1") (pin "4") (pinfunction "4_4") (pintype "unspecified"))
    )
    (net (code "93") (name "Net-(R59-Pad1)") (class "Default")
      (node (ref "R59") (pin "1") (pinfunction "1_1") (pintype "input"))
      (node (ref "R63") (pin "1") (pinfunction "1_1") (pintype "input"))
      (node (ref "SW1") (pin "5") (pinfunction "5_5") (pintype "unspecified"))
    )
    (net (code "94") (name "Net-(R60-Pad1)") (class "Default")
      (node (ref "R60") (pin "1") (pinfunction "1_1") (pintype "input"))
      (node (ref "R61") (pin "2") (pinfunction "2_2") (pintype "input"))
      (node (ref "SW1") (pin "8") (pinfunction "8_8") (pintype "unspecified"))
    )
    (net (code "95") (name "Net-(R61-Pad1)") (class "Default")
      (node (ref "R61") (pin "1") (pinfunction "1_1") (pintype "input"))
      (node (ref "R62") (pin "2") (pinfunction "2_2") (pintype "input"))
      (node (ref "SW1") (pin "7") (pinfunction "7_7") (pintype "unspecified"))
    )
    (net (code "96") (name "Net-(R62-Pad1)") (class "Default")
      (node (ref "R62") (pin "1") (pinfunction "1_1") (pintype "input"))
      (node (ref "R63") (pin "2") (pinfunction "2_2") (pintype "input"))
      (node (ref "SW1") (pin "6") (pinfunction "6_6") (pintype "unspecified"))
    )
    (net (code "97") (name "Net-(R64-Pad1)") (class "Default")
      (node (ref "R64") (pin "1") (pinfunction "1_1") (pintype "input"))
      (node (ref "R65") (pin "2") (pinfunction "2_2") (pintype "input"))
      (node (ref "SW2") (pin "3") (pinfunction "3_3") (pintype "unspecified"))
    )
    (net (code "98") (name "Net-(R65-Pad1)") (class "Default")
      (node (ref "R65") (pin "1") (pinfunction "1_1") (pintype "input"))
      (node (ref "R66") (pin "2") (pinfunction "2_2") (pintype "input"))
      (node (ref "SW2") (pin "4") (pinfunction "4_4") (pintype "unspecified"))
    )
    (net (code "99") (name "Net-(R66-Pad1)") (class "Default")
      (node (ref "R66") (pin "1") (pinfunction "1_1") (pintype "input"))
      (node (ref "R70") (pin "1") (pinfunction "1_1") (pintype "input"))
      (node (ref "SW2") (pin "5") (pinfunction "5_5") (pintype "unspecified"))
    )
    (net (code "100") (name "Net-(R67-Pad1)") (class "Default")
      (node (ref "R67") (pin "1") (pinfunction "1_1") (pintype "input"))
      (node (ref "R68") (pin "2") (pinfunction "2_2") (pintype "input"))
      (node (ref "SW2") (pin "8") (pinfunction "8_8") (pintype "unspecified"))
    )
    (net (code "101") (name "Net-(R68-Pad1)") (class "Default")
      (node (ref "R68") (pin "1") (pinfunction "1_1") (pintype "input"))
      (node (ref "R69") (pin "2") (pinfunction "2_2") (pintype "input"))
      (node (ref "SW2") (pin "7") (pinfunction "7_7") (pintype "unspecified"))
    )
    (net (code "102") (name "Net-(R69-Pad1)") (class "Default")
      (node (ref "R69") (pin "1") (pinfunction "1_1") (pintype "input"))
      (node (ref "R70") (pin "2") (pinfunction "2_2") (pintype "input"))
      (node (ref "SW2") (pin "6") (pinfunction "6_6") (pintype "unspecified"))
    )
    (net (code "103") (name "Net-(U5-OE#)") (class "Default")
      (node (ref "R37") (pin "2") (pinfunction "2_2") (pintype "input"))
      (node (ref "U5") (pin "23") (pinfunction "OE#_23") (pintype "unspecified"))
    )
    (net (code "104") (name "Net-(U6-FB)") (class "Default")
      (node (ref "C8") (pin "1") (pinfunction "1_1") (pintype "unspecified"))
      (node (ref "R1") (pin "1") (pinfunction "1_1") (pintype "input"))
      (node (ref "R2") (pin "2") (pinfunction "2_2") (pintype "input"))
      (node (ref "U6") (pin "4") (pinfunction "FB_4") (pintype "unspecified"))
    )
    (net (code "105") (name "Net-(U6-PG)") (class "Default")
      (node (ref "R3") (pin "1") (pinfunction "1_1") (pintype "input"))
      (node (ref "R4") (pin "2") (pinfunction "2_2") (pintype "input"))
      (node (ref "U6") (pin "6") (pinfunction "PG_6") (pintype "unspecified"))
    )
    (net (code "106") (name "Net-(U6-SW)") (class "Default")
      (node (ref "L1") (pin "1") (pinfunction "1_1") (pintype "unspecified"))
      (node (ref "U6") (pin "2") (pinfunction "SW_2") (pintype "passive"))
    )
    (net (code "107") (name "PWM1") (class "Default")
      (node (ref "U3") (pin "1") (pinfunction "1B_1") (pintype "unspecified"))
      (node (ref "U5") (pin "6") (pinfunction "LED0_6") (pintype "unspecified"))
    )
    (net (code "108") (name "PWM2") (class "Default")
      (node (ref "U3") (pin "2") (pinfunction "2B_2") (pintype "unspecified"))
      (node (ref "U5") (pin "7") (pinfunction "LED1_7") (pintype "unspecified"))
    )
    (net (code "109") (name "PWM3") (class "Default")
      (node (ref "U3") (pin "3") (pinfunction "3B_3") (pintype "unspecified"))
      (node (ref "U5") (pin "8") (pinfunction "LED2_8") (pintype "unspecified"))
    )
    (net (code "110") (name "PWM4") (class "Default")
      (node (ref "U3") (pin "4") (pinfunction "4B_4") (pintype "unspecified"))
      (node (ref "U5") (pin "9") (pinfunction "LED3_9") (pintype "unspecified"))
    )
    (net (code "111") (name "PWM5") (class "Default")
      (node (ref "U3") (pin "5") (pinfunction "5B_5") (pintype "unspecified"))
      (node (ref "U5") (pin "10") (pinfunction "LED4_10") (pintype "unspecified"))
    )
    (net (code "112") (name "PWM6") (class "Default")
      (node (ref "U3") (pin "6") (pinfunction "6B_6") (pintype "unspecified"))
      (node (ref "U5") (pin "11") (pinfunction "LED5_11") (pintype "unspecified"))
    )
    (net (code "113") (name "PWM7") (class "Default")
      (node (ref "U3") (pin "7") (pinfunction "7B_7") (pintype "unspecified"))
      (node (ref "U5") (pin "12") (pinfunction "LED6_12") (pintype "unspecified"))
    )
    (net (code "114") (name "PWM8") (class "Default")
      (node (ref "U3") (pin "8") (pinfunction "8B_8") (pintype "unspecified"))
      (node (ref "U5") (pin "13") (pinfunction "LED7_13") (pintype "unspecified"))
    )
    (net (code "115") (name "PWM9") (class "Default")
      (node (ref "R36") (pin "1") (pinfunction "1_1") (pintype "input"))
      (node (ref "U5") (pin "15") (pinfunction "LED8_15") (pintype "unspecified"))
    )
    (net (code "116") (name "PWM10") (class "Default")
      (node (ref "H4") (pin "1") (pinfunction "1_1") (pintype "unspecified"))
      (node (ref "U5") (pin "16") (pinfunction "LED9_16") (pintype "unspecified"))
    )
    (net (code "117") (name "PWM11") (class "Default")
      (node (ref "H4") (pin "2") (pinfunction "2_2") (pintype "unspecified"))
      (node (ref "U5") (pin "17") (pinfunction "LED10_17") (pintype "unspecified"))
    )
    (net (code "118") (name "PWM12") (class "Default")
      (node (ref "H4") (pin "3") (pinfunction "3_3") (pintype "unspecified"))
      (node (ref "U5") (pin "18") (pinfunction "LED11_18") (pintype "unspecified"))
    )
    (net (code "119") (name "PWM13") (class "Default")
      (node (ref "H4") (pin "4") (pinfunction "4_4") (pintype "unspecified"))
      (node (ref "U5") (pin "19") (pinfunction "LED12_19") (pintype "unspecified"))
    )
    (net (code "120") (name "PWM14") (class "Default")
      (node (ref "H4") (pin "5") (pinfunction "5_5") (pintype "unspecified"))
      (node (ref "U5") (pin "20") (pinfunction "LED13_20") (pintype "unspecified"))
    )
    (net (code "121") (name "PWM15") (class "Default")
      (node (ref "H4") (pin "6") (pinfunction "6_6") (pintype "unspecified"))
      (node (ref "U5") (pin "21") (pinfunction "LED14_21") (pintype "unspecified"))
    )
    (net (code "122") (name "PWM16") (class "Default")
      (node (ref "H4") (pin "7") (pinfunction "7_7") (pintype "unspecified"))
      (node (ref "U5") (pin "22") (pinfunction "LED15_22") (pintype "unspecified"))
    )
    (net (code "123") (name "SCL") (class "Default")
      (node (ref "DISPLAY1") (pin "3") (pinfunction "SCL_3") (pintype "unspecified"))
      (node (ref "R39") (pin "1") (pinfunction "1_1") (pintype "input"))
      (node (ref "U5") (pin "26") (pinfunction "SCL_26") (pintype "unspecified"))
    )
    (net (code "124") (name "SDA") (class "Default")
      (node (ref "DISPLAY1") (pin "4") (pinfunction "SDA_4") (pintype "unspecified"))
      (node (ref "R38") (pin "1") (pinfunction "1_1") (pintype "input"))
      (node (ref "U5") (pin "27") (pinfunction "SDA_27") (pintype "unspecified"))
    )
    (net (code "125") (name "TactSwitchLP1") (class "Default")
      (node (ref "C17") (pin "2") (pinfunction "2_2") (pintype "input"))
      (node (ref "R17") (pin "2") (pinfunction "2_2") (pintype "unspecified"))
      (node (ref "U1") (pin "1") (pinfunction "1A_1") (pintype "unspecified"))
    )
    (net (code "126") (name "TactSwitchLP2") (class "Default")
      (node (ref "C18") (pin "2") (pinfunction "2_2") (pintype "input"))
      (node (ref "R18") (pin "2") (pinfunction "2_2") (pintype "unspecified"))
      (node (ref "U1") (pin "3") (pinfunction "2A_3") (pintype "unspecified"))
    )
    (net (code "127") (name "TactSwitchLP3") (class "Default")
      (node (ref "C19") (pin "2") (pinfunction "2_2") (pintype "input"))
      (node (ref "R19") (pin "2") (pinfunction "2_2") (pintype "unspecified"))
      (node (ref "U1") (pin "5") (pinfunction "3A_5") (pintype "unspecified"))
    )
    (net (code "128") (name "TactSwitchLP4") (class "Default")
      (node (ref "C20") (pin "2") (pinfunction "2_2") (pintype "input"))
      (node (ref "R20") (pin "2") (pinfunction "2_2") (pintype "unspecified"))
      (node (ref "U1") (pin "9") (pinfunction "4A_9") (pintype "unspecified"))
    )
    (net (code "129") (name "TactSwitchLP5") (class "Default")
      (node (ref "C21") (pin "2") (pinfunction "2_2") (pintype "input"))
      (node (ref "R24") (pin "2") (pinfunction "2_2") (pintype "unspecified"))
      (node (ref "U1") (pin "11") (pinfunction "5A_11") (pintype "unspecified"))
    )
    (net (code "130") (name "TactSwitchLP6") (class "Default")
      (node (ref "C22") (pin "2") (pinfunction "2_2") (pintype "input"))
      (node (ref "R23") (pin "2") (pinfunction "2_2") (pintype "unspecified"))
      (node (ref "U1") (pin "13") (pinfunction "6A_13") (pintype "unspecified"))
    )
    (net (code "131") (name "TactSwitchLP7") (class "Default")
      (node (ref "C23") (pin "2") (pinfunction "2_2") (pintype "input"))
      (node (ref "R22") (pin "2") (pinfunction "2_2") (pintype "unspecified"))
      (node (ref "U2") (pin "1") (pinfunction "1A_1") (pintype "unspecified"))
    )
    (net (code "132") (name "TactSwitchLP8") (class "Default")
      (node (ref "C24") (pin "2") (pinfunction "2_2") (pintype "input"))
      (node (ref "R21") (pin "2") (pinfunction "2_2") (pintype "unspecified"))
      (node (ref "U2") (pin "3") (pinfunction "2A_3") (pintype "unspecified"))
    )
    (net (code "133") (name "TactSwitchLP9") (class "Default")
      (node (ref "C27") (pin "2") (pinfunction "2_2") (pintype "input"))
      (node (ref "R25") (pin "2") (pinfunction "2_2") (pintype "unspecified"))
      (node (ref "U2") (pin "5") (pinfunction "3A_5") (pintype "unspecified"))
    )
    (net (code "134") (name "TactSwitchLP10") (class "Default")
      (node (ref "C26") (pin "2") (pinfunction "2_2") (pintype "input"))
      (node (ref "R26") (pin "2") (pinfunction "2_2") (pintype "unspecified"))
      (node (ref "U2") (pin "9") (pinfunction "4A_9") (pintype "unspecified"))
    )
    (net (code "135") (name "TactSwitchLP11") (class "Default")
      (node (ref "C25") (pin "2") (pinfunction "2_2") (pintype "input"))
      (node (ref "R27") (pin "2") (pinfunction "2_2") (pintype "unspecified"))
      (node (ref "U2") (pin "11") (pinfunction "5A_11") (pintype "unspecified"))
    )
    (net (code "136") (name "TactSwitchST1") (class "Default")
      (node (ref "U1") (pin "2") (pinfunction "1Y_2") (pintype "unspecified"))
      (node (ref "U7") (pin "2") (pinfunction "D0_2") (pintype "unspecified"))
    )
    (net (code "137") (name "TactSwitchST2") (class "Default")
      (node (ref "U1") (pin "4") (pinfunction "2Y_4") (pintype "unspecified"))
      (node (ref "U7") (pin "3") (pinfunction "D1_3") (pintype "unspecified"))
    )
    (net (code "138") (name "TactSwitchST3") (class "Default")
      (node (ref "U1") (pin "6") (pinfunction "3Y_6") (pintype "unspecified"))
      (node (ref "U7") (pin "4") (pinfunction "D2_4") (pintype "unspecified"))
    )
    (net (code "139") (name "TactSwitchST4") (class "Default")
      (node (ref "U1") (pin "8") (pinfunction "4Y_8") (pintype "unspecified"))
      (node (ref "U7") (pin "5") (pinfunction "D3_5") (pintype "unspecified"))
    )
    (net (code "140") (name "TactSwitchST5") (class "Default")
      (node (ref "U1") (pin "10") (pinfunction "5Y_10") (pintype "unspecified"))
      (node (ref "U7") (pin "10") (pinfunction "D4_10") (pintype "unspecified"))
    )
    (net (code "141") (name "TactSwitchST6") (class "Default")
      (node (ref "U1") (pin "12") (pinfunction "6Y_12") (pintype "unspecified"))
      (node (ref "U7") (pin "11") (pinfunction "D5_11") (pintype "unspecified"))
    )
    (net (code "142") (name "TactSwitchST7") (class "Default")
      (node (ref "U2") (pin "2") (pinfunction "1Y_2") (pintype "unspecified"))
      (node (ref "U7") (pin "12") (pinfunction "D6_12") (pintype "unspecified"))
    )
    (net (code "143") (name "TactSwitchST8") (class "Default")
      (node (ref "U2") (pin "4") (pinfunction "2Y_4") (pintype "unspecified"))
      (node (ref "U7") (pin "14") (pinfunction "D7_14") (pintype "unspecified"))
    )
    (net (code "144") (name "TactSwitchST9") (class "Default")
      (node (ref "U2") (pin "6") (pinfunction "3Y_6") (pintype "unspecified"))
      (node (ref "U8") (pin "2") (pinfunction "D0_2") (pintype "unspecified"))
    )
    (net (code "145") (name "TactSwitchST10") (class "Default")
      (node (ref "U2") (pin "8") (pinfunction "4Y_8") (pintype "unspecified"))
      (node (ref "U8") (pin "3") (pinfunction "D1_3") (pintype "unspecified"))
    )
    (net (code "146") (name "TactSwitchST11") (class "Default")
      (node (ref "U2") (pin "10") (pinfunction "5Y_10") (pintype "unspecified"))
      (node (ref "U8") (pin "4") (pinfunction "D2_4") (pintype "unspecified"))
    )
    (net (code "147") (name "analogInPot") (class "Default")
      (node (ref "C16") (pin "2") (pinfunction "2_2") (pintype "input"))
      (node (ref "H5") (pin "1") (pinfunction "1_1") (pintype "unspecified"))
      (node (ref "R46") (pin "1") (pinfunction "1_1") (pintype "input"))
      (node (ref "R5") (pin "2") (pinfunction "2_2") (pintype "unspecified"))
    )
    (net (code "148") (name "analogInSW1") (class "Default")
      (node (ref "C9") (pin "2") (pinfunction "2_2") (pintype "input"))
      (node (ref "H5") (pin "3") (pinfunction "3_3") (pintype "unspecified"))
      (node (ref "R48") (pin "1") (pinfunction "1_1") (pintype "input"))
      (node (ref "SW1") (pin "1") (pinfunction "1_1") (pintype "unspecified"))
      (node (ref "SW1") (pin "10") (pinfunction "10_10") (pintype "unspecified"))
    )
    (net (code "149") (name "analogInSW2") (class "Default")
      (node (ref "C10") (pin "2") (pinfunction "2_2") (pintype "input"))
      (node (ref "H5") (pin "2") (pinfunction "2_2") (pintype "unspecified"))
      (node (ref "R47") (pin "1") (pinfunction "1_1") (pintype "input"))
      (node (ref "SW2") (pin "1") (pinfunction "1_1") (pintype "unspecified"))
      (node (ref "SW2") (pin "10") (pinfunction "10_10") (pintype "unspecified"))
    )
    (net (code "150") (name "unconnected-(R5-EH-Pad4)") (class "Default")
      (node (ref "R5") (pin "4") (pinfunction "EH_4") (pintype "unspecified+no_connect"))
    )
    (net (code "151") (name "unconnected-(R5-EH-Pad5)") (class "Default")
      (node (ref "R5") (pin "5") (pinfunction "EH_5") (pintype "unspecified+no_connect"))
    )
    (net (code "152") (name "unconnected-(SW3-Pad1)") (class "Default")
      (node (ref "SW3") (pin "1") (pinfunction "1_1") (pintype "unspecified+no_connect"))
    )
    (net (code "153") (name "unconnected-(SW3-Pad3)") (class "Default")
      (node (ref "SW3") (pin "3") (pinfunction "3_3") (pintype "unspecified+no_connect"))
    )
    (net (code "154") (name "unconnected-(SW4-Pad1)") (class "Default")
      (node (ref "SW4") (pin "1") (pinfunction "1_1") (pintype "unspecified+no_connect"))
    )
    (net (code "155") (name "unconnected-(SW4-Pad3)") (class "Default")
      (node (ref "SW4") (pin "3") (pinfunction "3_3") (pintype "unspecified+no_connect"))
    )
    (net (code "156") (name "unconnected-(SW5-Pad1)") (class "Default")
      (node (ref "SW5") (pin "1") (pinfunction "1_1") (pintype "unspecified+no_connect"))
    )
    (net (code "157") (name "unconnected-(SW5-Pad3)") (class "Default")
      (node (ref "SW5") (pin "3") (pinfunction "3_3") (pintype "unspecified+no_connect"))
    )
    (net (code "158") (name "unconnected-(SW6-Pad1)") (class "Default")
      (node (ref "SW6") (pin "1") (pinfunction "1_1") (pintype "unspecified+no_connect"))
    )
    (net (code "159") (name "unconnected-(SW6-Pad3)") (class "Default")
      (node (ref "SW6") (pin "3") (pinfunction "3_3") (pintype "unspecified+no_connect"))
    )
    (net (code "160") (name "unconnected-(SW7-Pad1)") (class "Default")
      (node (ref "SW7") (pin "1") (pinfunction "1_1") (pintype "unspecified+no_connect"))
    )
    (net (code "161") (name "unconnected-(SW7-Pad3)") (class "Default")
      (node (ref "SW7") (pin "3") (pinfunction "3_3") (pintype "unspecified+no_connect"))
    )
    (net (code "162") (name "unconnected-(SW8-Pad1)") (class "Default")
      (node (ref "SW8") (pin "1") (pinfunction "1_1") (pintype "unspecified+no_connect"))
    )
    (net (code "163") (name "unconnected-(SW8-Pad3)") (class "Default")
      (node (ref "SW8") (pin "3") (pinfunction "3_3") (pintype "unspecified+no_connect"))
    )
    (net (code "164") (name "unconnected-(SW9-Pad1)") (class "Default")
      (node (ref "SW9") (pin "1") (pinfunction "1_1") (pintype "unspecified+no_connect"))
    )
    (net (code "165") (name "unconnected-(SW9-Pad3)") (class "Default")
      (node (ref "SW9") (pin "3") (pinfunction "3_3") (pintype "unspecified+no_connect"))
    )
    (net (code "166") (name "unconnected-(SW10-Pad1)") (class "Default")
      (node (ref "SW10") (pin "1") (pinfunction "1_1") (pintype "unspecified+no_connect"))
    )
    (net (code "167") (name "unconnected-(SW10-Pad3)") (class "Default")
      (node (ref "SW10") (pin "3") (pinfunction "3_3") (pintype "unspecified+no_connect"))
    )
    (net (code "168") (name "unconnected-(SW11-Pad1)") (class "Default")
      (node (ref "SW11") (pin "1") (pinfunction "1_1") (pintype "unspecified+no_connect"))
    )
    (net (code "169") (name "unconnected-(SW11-Pad3)") (class "Default")
      (node (ref "SW11") (pin "3") (pinfunction "3_3") (pintype "unspecified+no_connect"))
    )
    (net (code "170") (name "unconnected-(SW12-Pad1)") (class "Default")
      (node (ref "SW12") (pin "1") (pinfunction "1_1") (pintype "unspecified+no_connect"))
    )
    (net (code "171") (name "unconnected-(SW12-Pad3)") (class "Default")
      (node (ref "SW12") (pin "3") (pinfunction "3_3") (pintype "unspecified+no_connect"))
    )
    (net (code "172") (name "unconnected-(SW13-Pad1)") (class "Default")
      (node (ref "SW13") (pin "1") (pinfunction "1_1") (pintype "unspecified+no_connect"))
    )
    (net (code "173") (name "unconnected-(SW13-Pad3)") (class "Default")
      (node (ref "SW13") (pin "3") (pinfunction "3_3") (pintype "unspecified+no_connect"))
    )
    (net (code "174") (name "unconnected-(SWSTEP1-Pad4)") (class "Default")
      (node (ref "SWSTEP1") (pin "4") (pinfunction "4_4") (pintype "unspecified+no_connect"))
    )
    (net (code "175") (name "unconnected-(SWSTEP1-Pad5)") (class "Default")
      (node (ref "SWSTEP1") (pin "5") (pinfunction "5_5") (pintype "unspecified+no_connect"))
    )
    (net (code "176") (name "unconnected-(SWSTEP1-Pad6)") (class "Default")
      (node (ref "SWSTEP1") (pin "6") (pinfunction "6_6") (pintype "unspecified+no_connect"))
    )
    (net (code "177") (name "unconnected-(SWSTEP1-Pad7)") (class "Default")
      (node (ref "SWSTEP1") (pin "7") (pinfunction "7_7") (pintype "unspecified+no_connect"))
    )
    (net (code "178") (name "unconnected-(U4-QH&apos;-Pad9)") (class "Default")
      (node (ref "U4") (pin "9") (pinfunction "QH&apos;_9") (pintype "unspecified+no_connect"))
    )
    (net (code "179") (name "unconnected-(U7-DS-Pad1)") (class "Default")
      (node (ref "U7") (pin "1") (pinfunction "DS_1") (pintype "unspecified+no_connect"))
    )
    (net (code "180") (name "unconnected-(USB1-D+-Pad3)") (class "Default")
      (node (ref "USB1") (pin "3") (pinfunction "D+_3") (pintype "unspecified+no_connect"))
    )
    (net (code "181") (name "unconnected-(USB1-D--Pad2)") (class "Default")
      (node (ref "USB1") (pin "2") (pinfunction "D-_2") (pintype "unspecified+no_connect"))
    )
    (net (code "182") (name "unconnected-(USB1-ID-Pad4)") (class "Default")
      (node (ref "USB1") (pin "4") (pinfunction "ID_4") (pintype "unspecified+no_connect"))
    )
  )
)
